# control.net
KiCad netlist of a schematic drawn in EAGLE
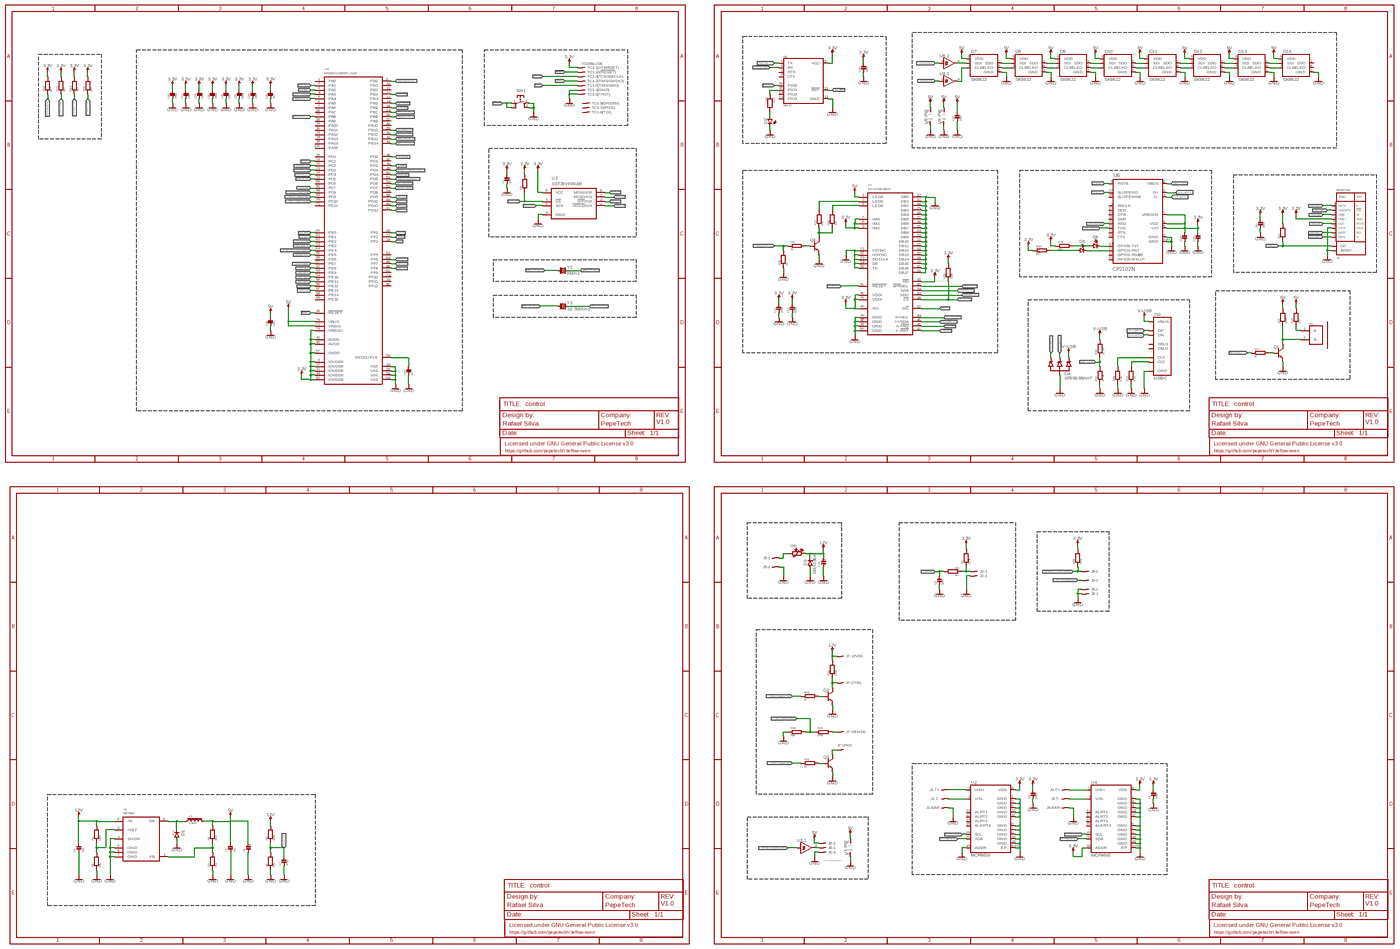
[diagram p0: schematic, sheet 1, overview]
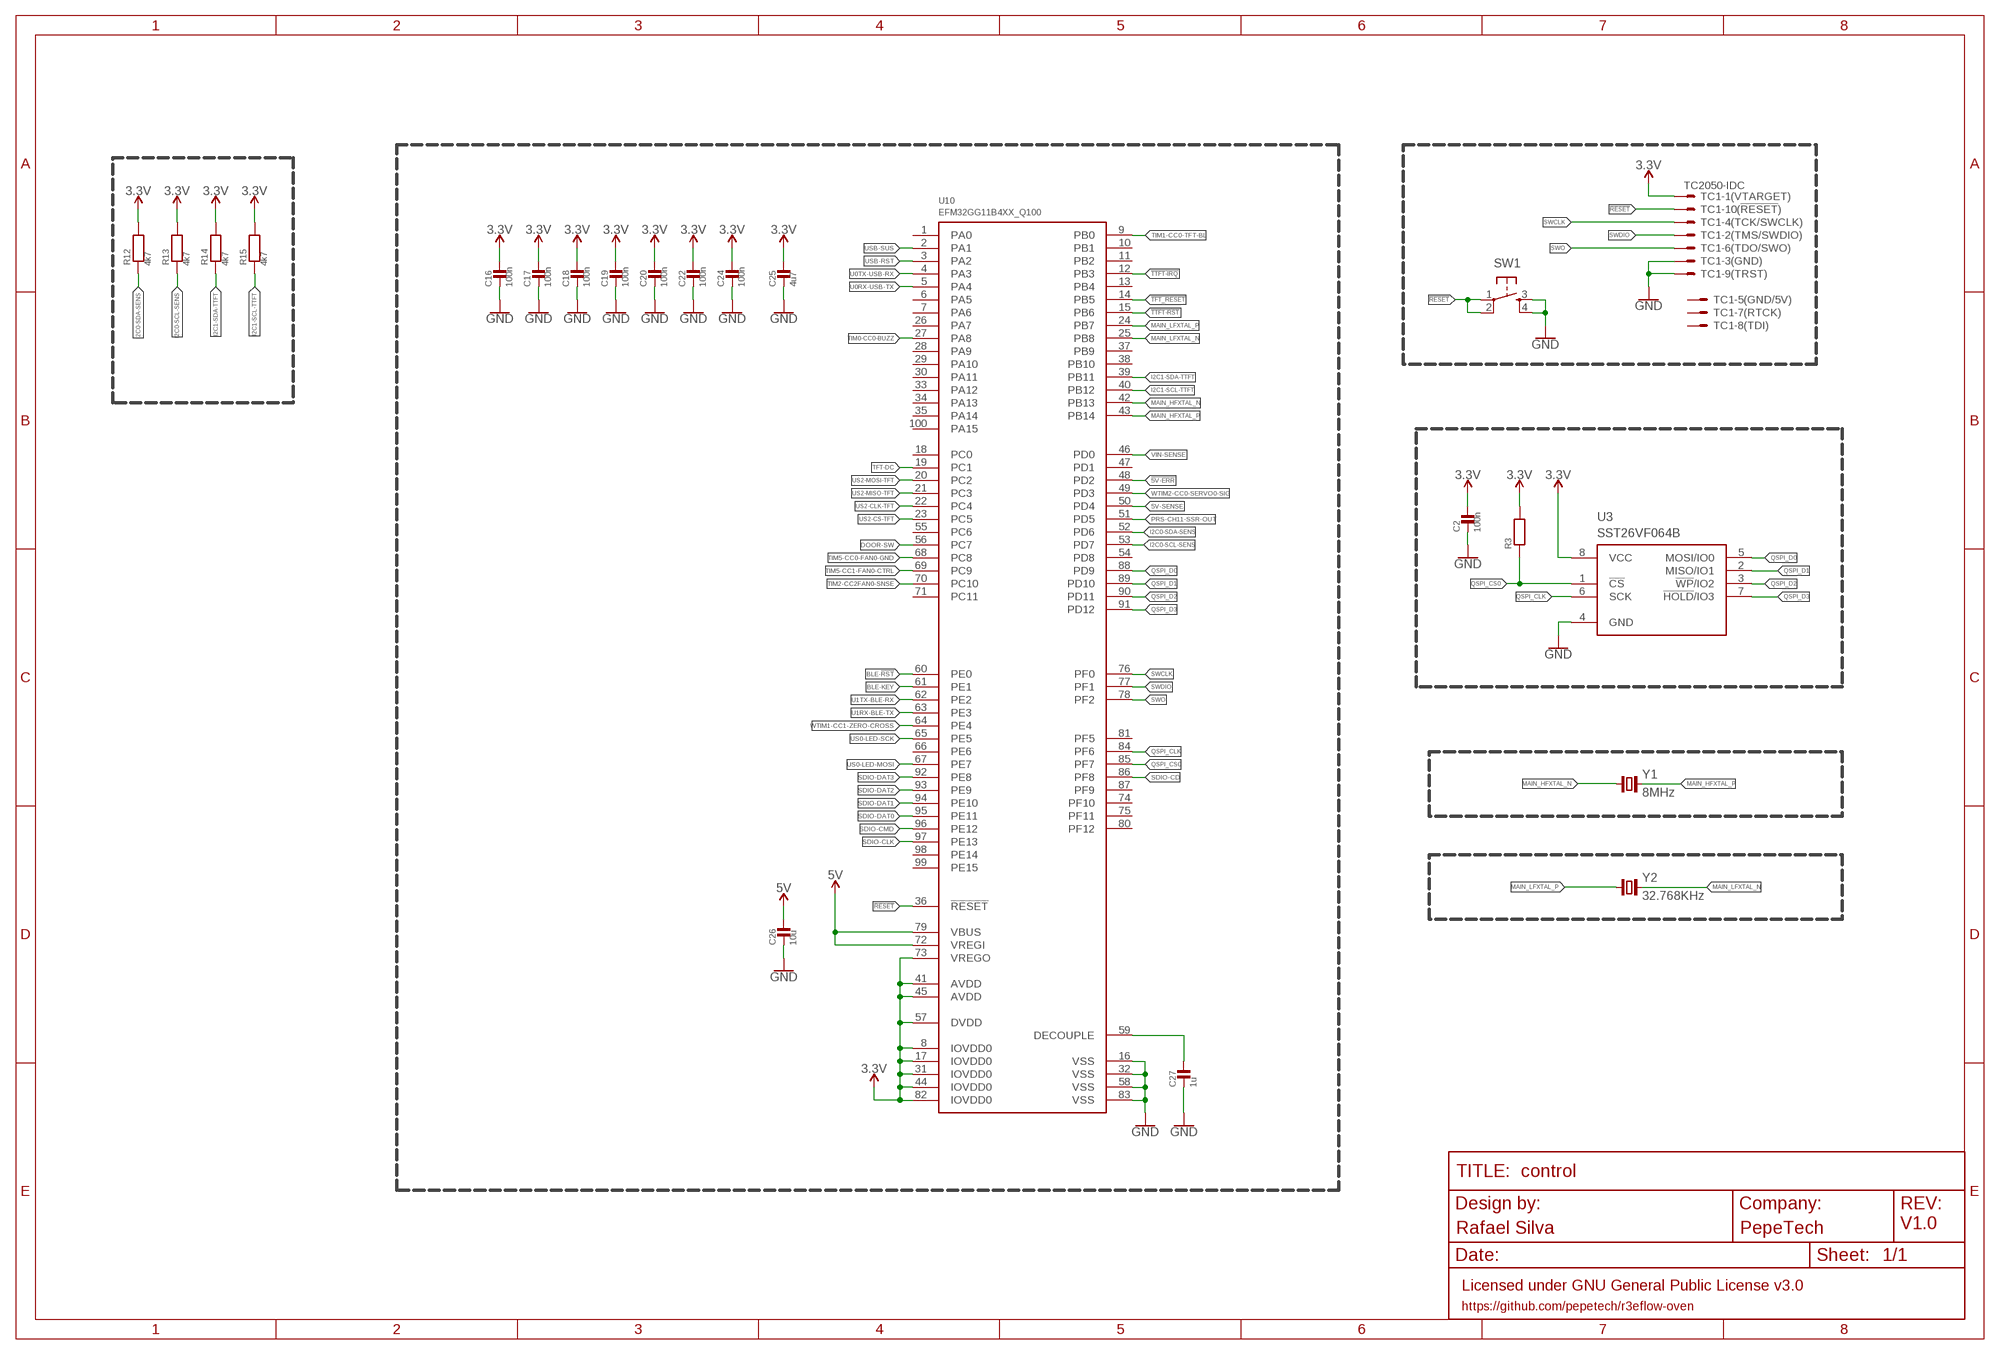
[diagram p1: schematic, sheet 1, part 1 of 4]
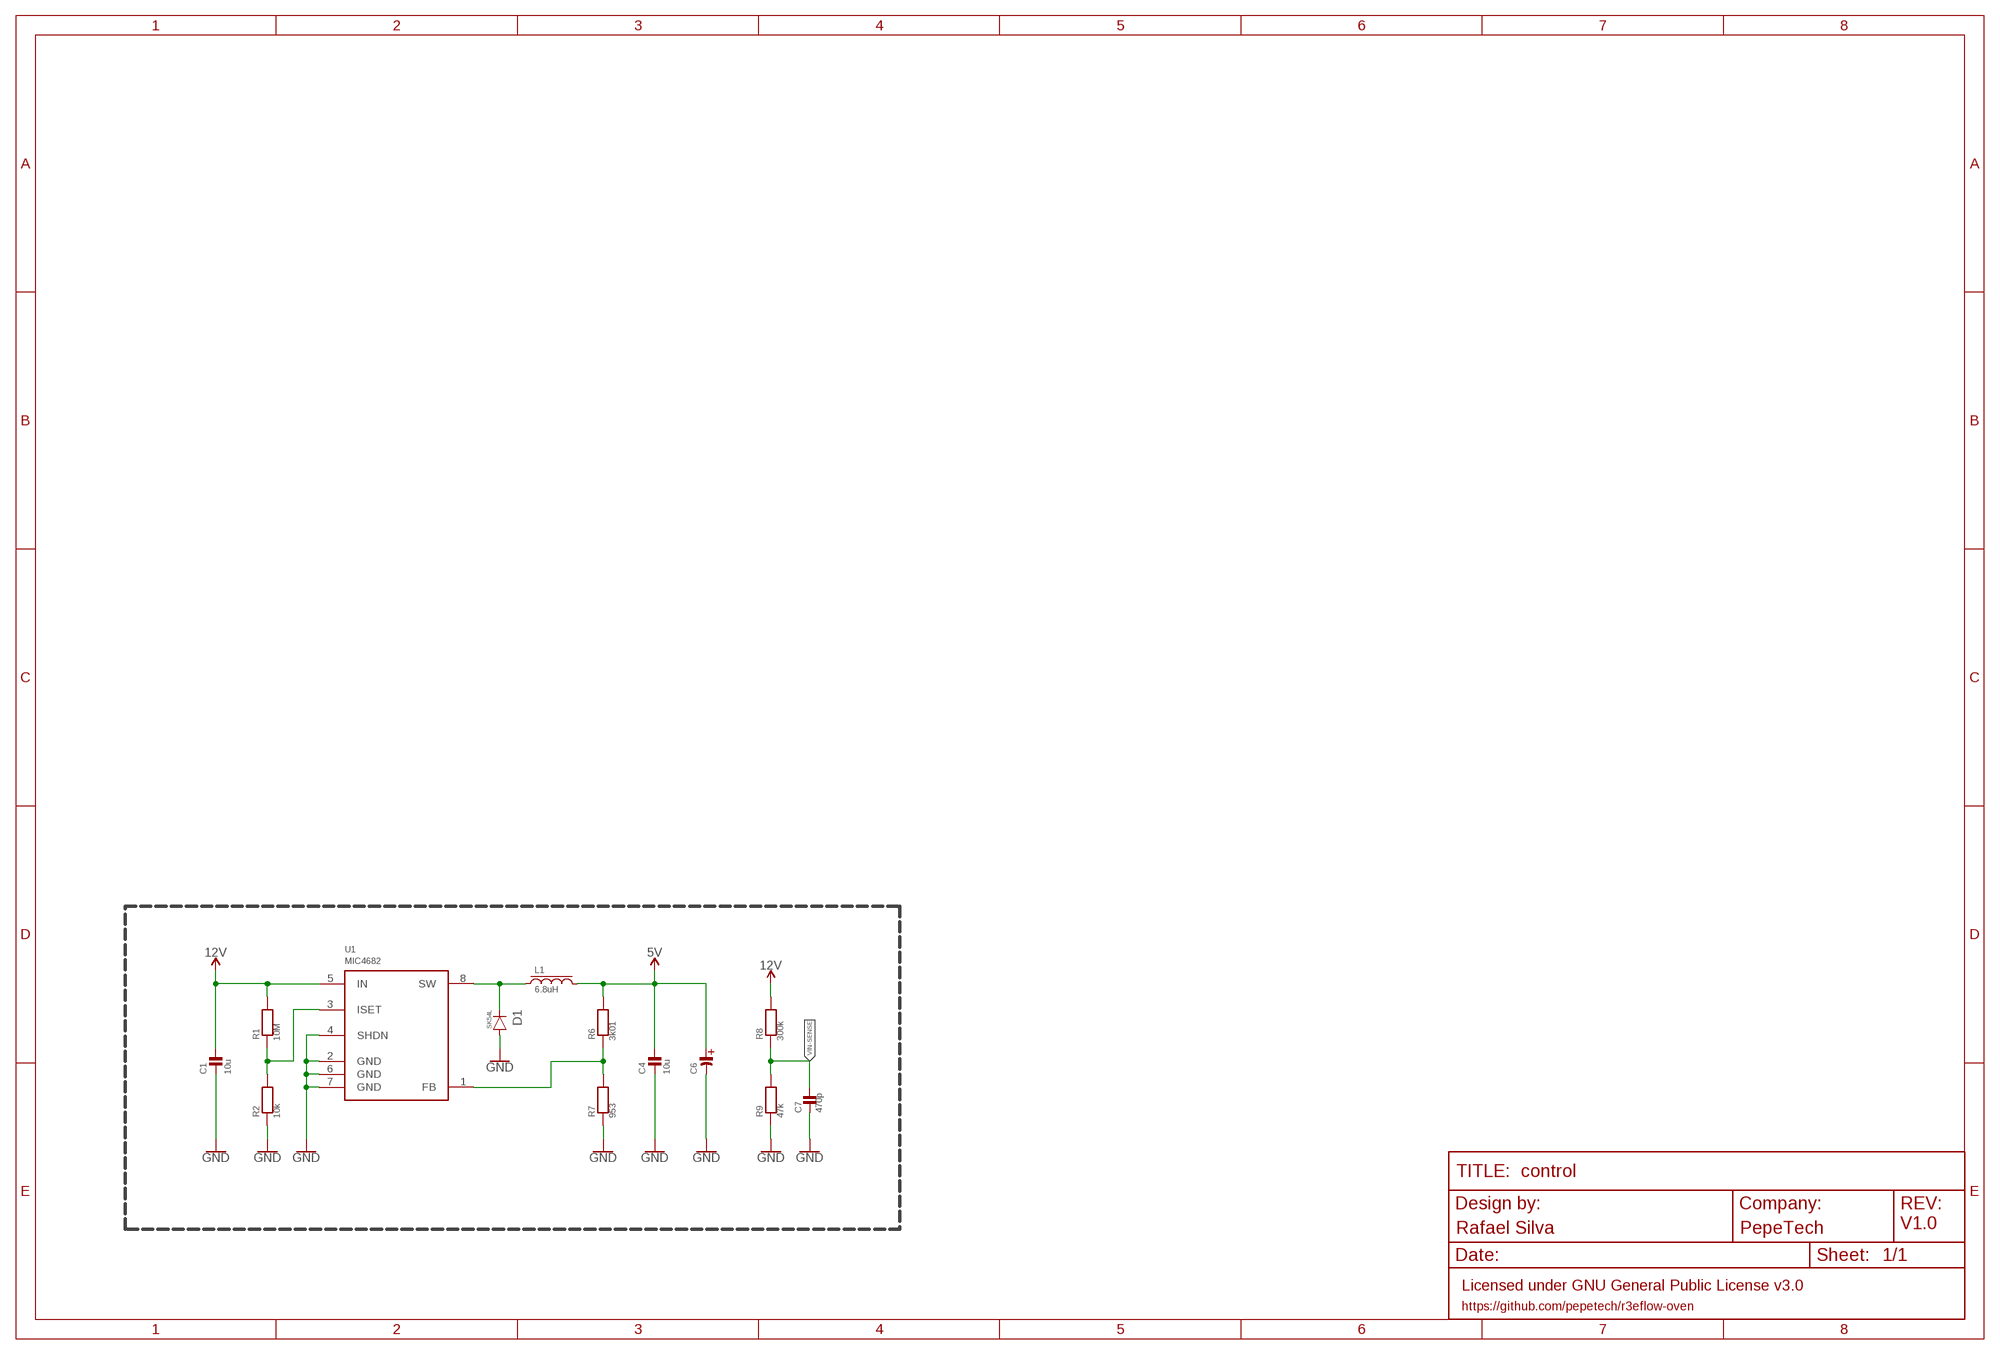
[diagram p2: schematic, sheet 1, part 2 of 4]
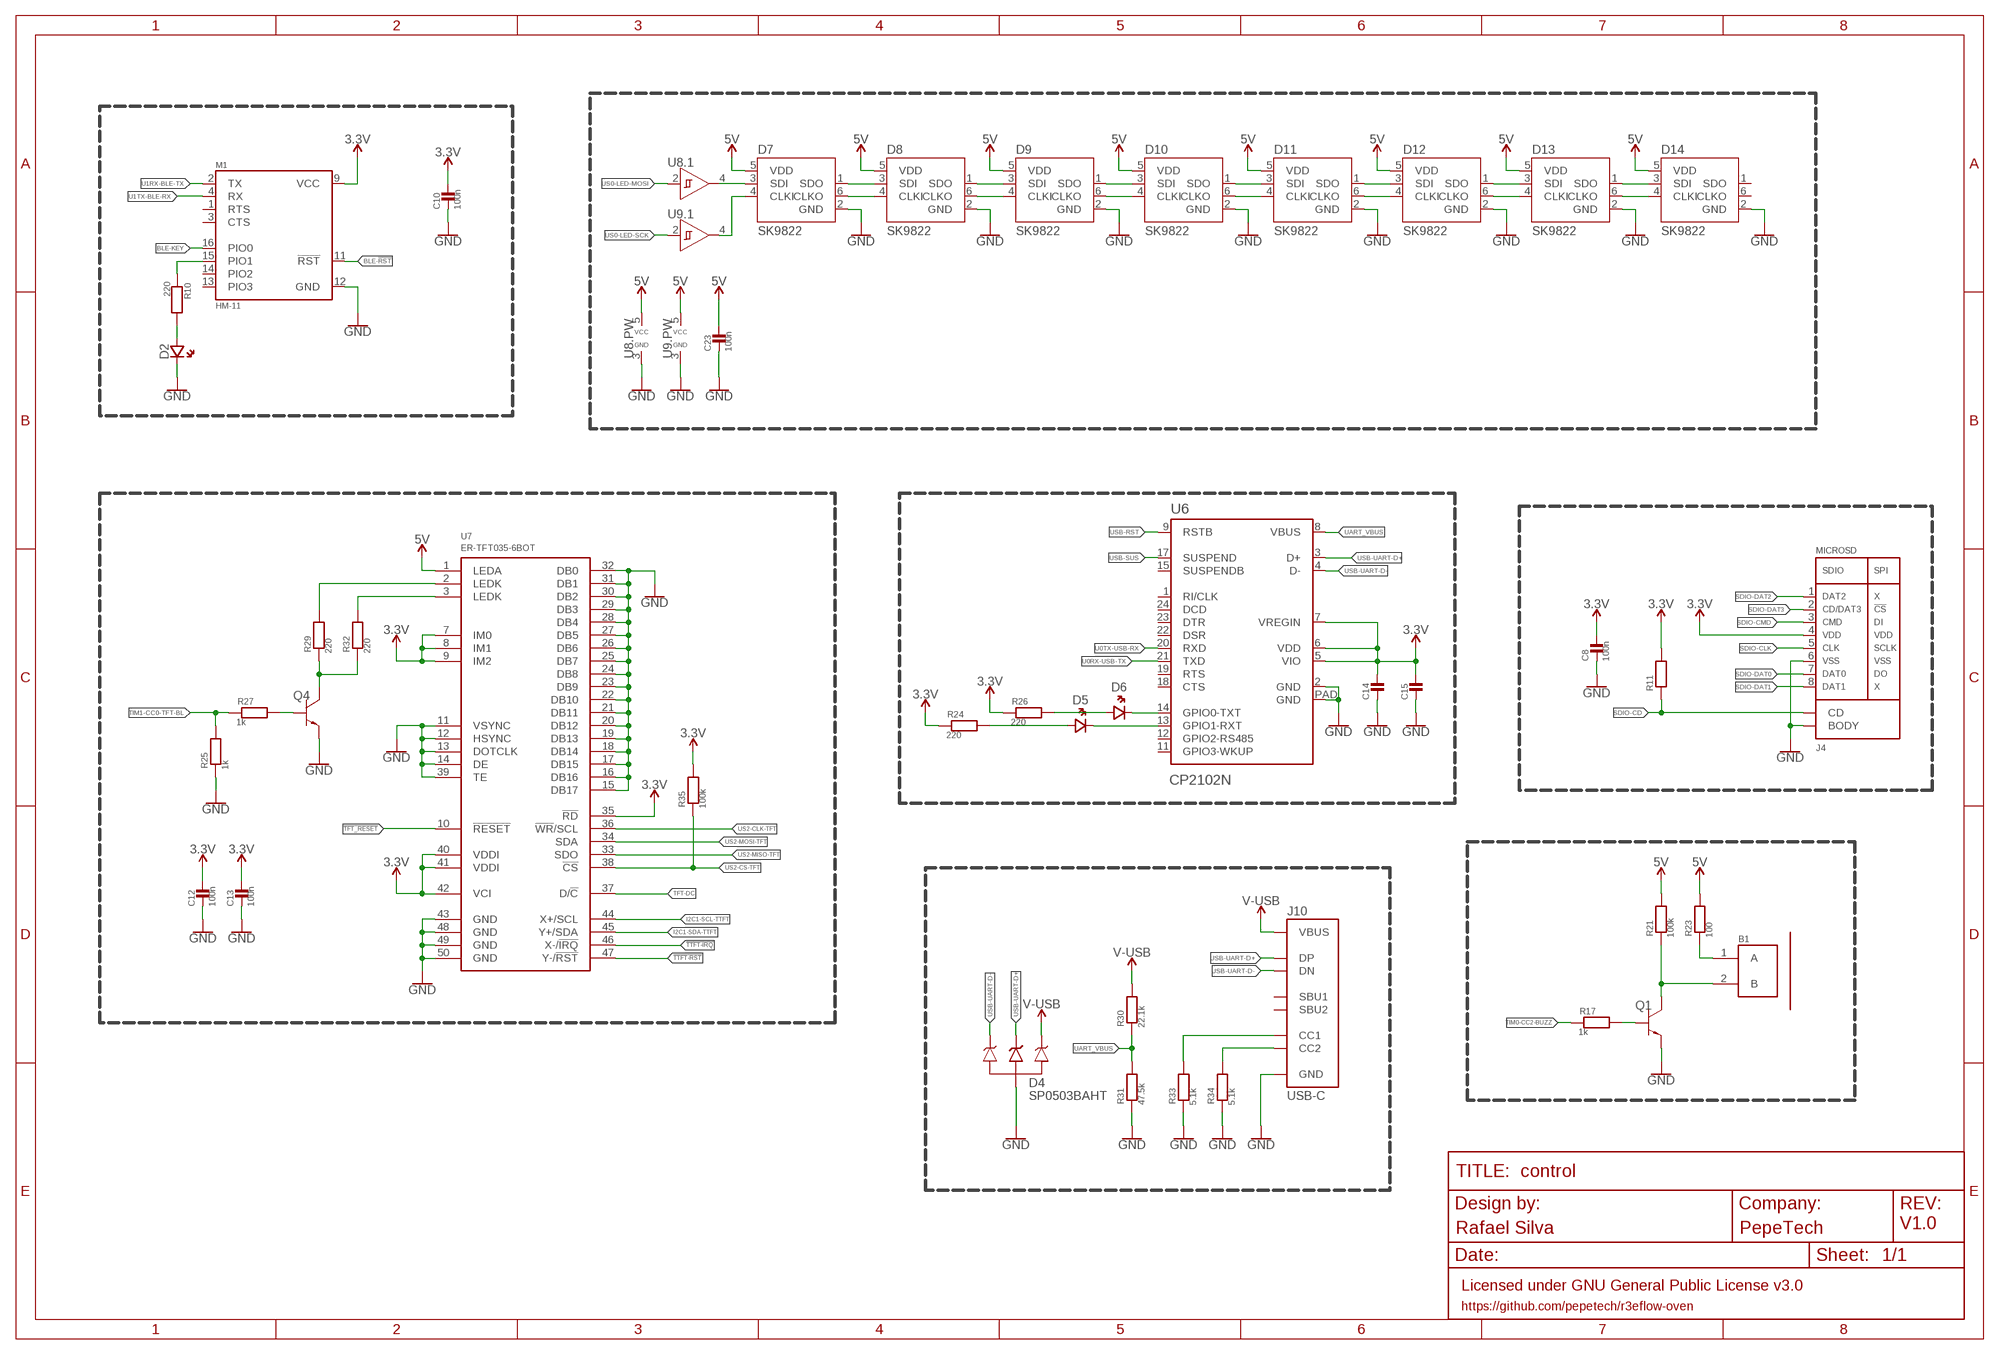
[diagram p3: schematic, sheet 1, part 3 of 4]
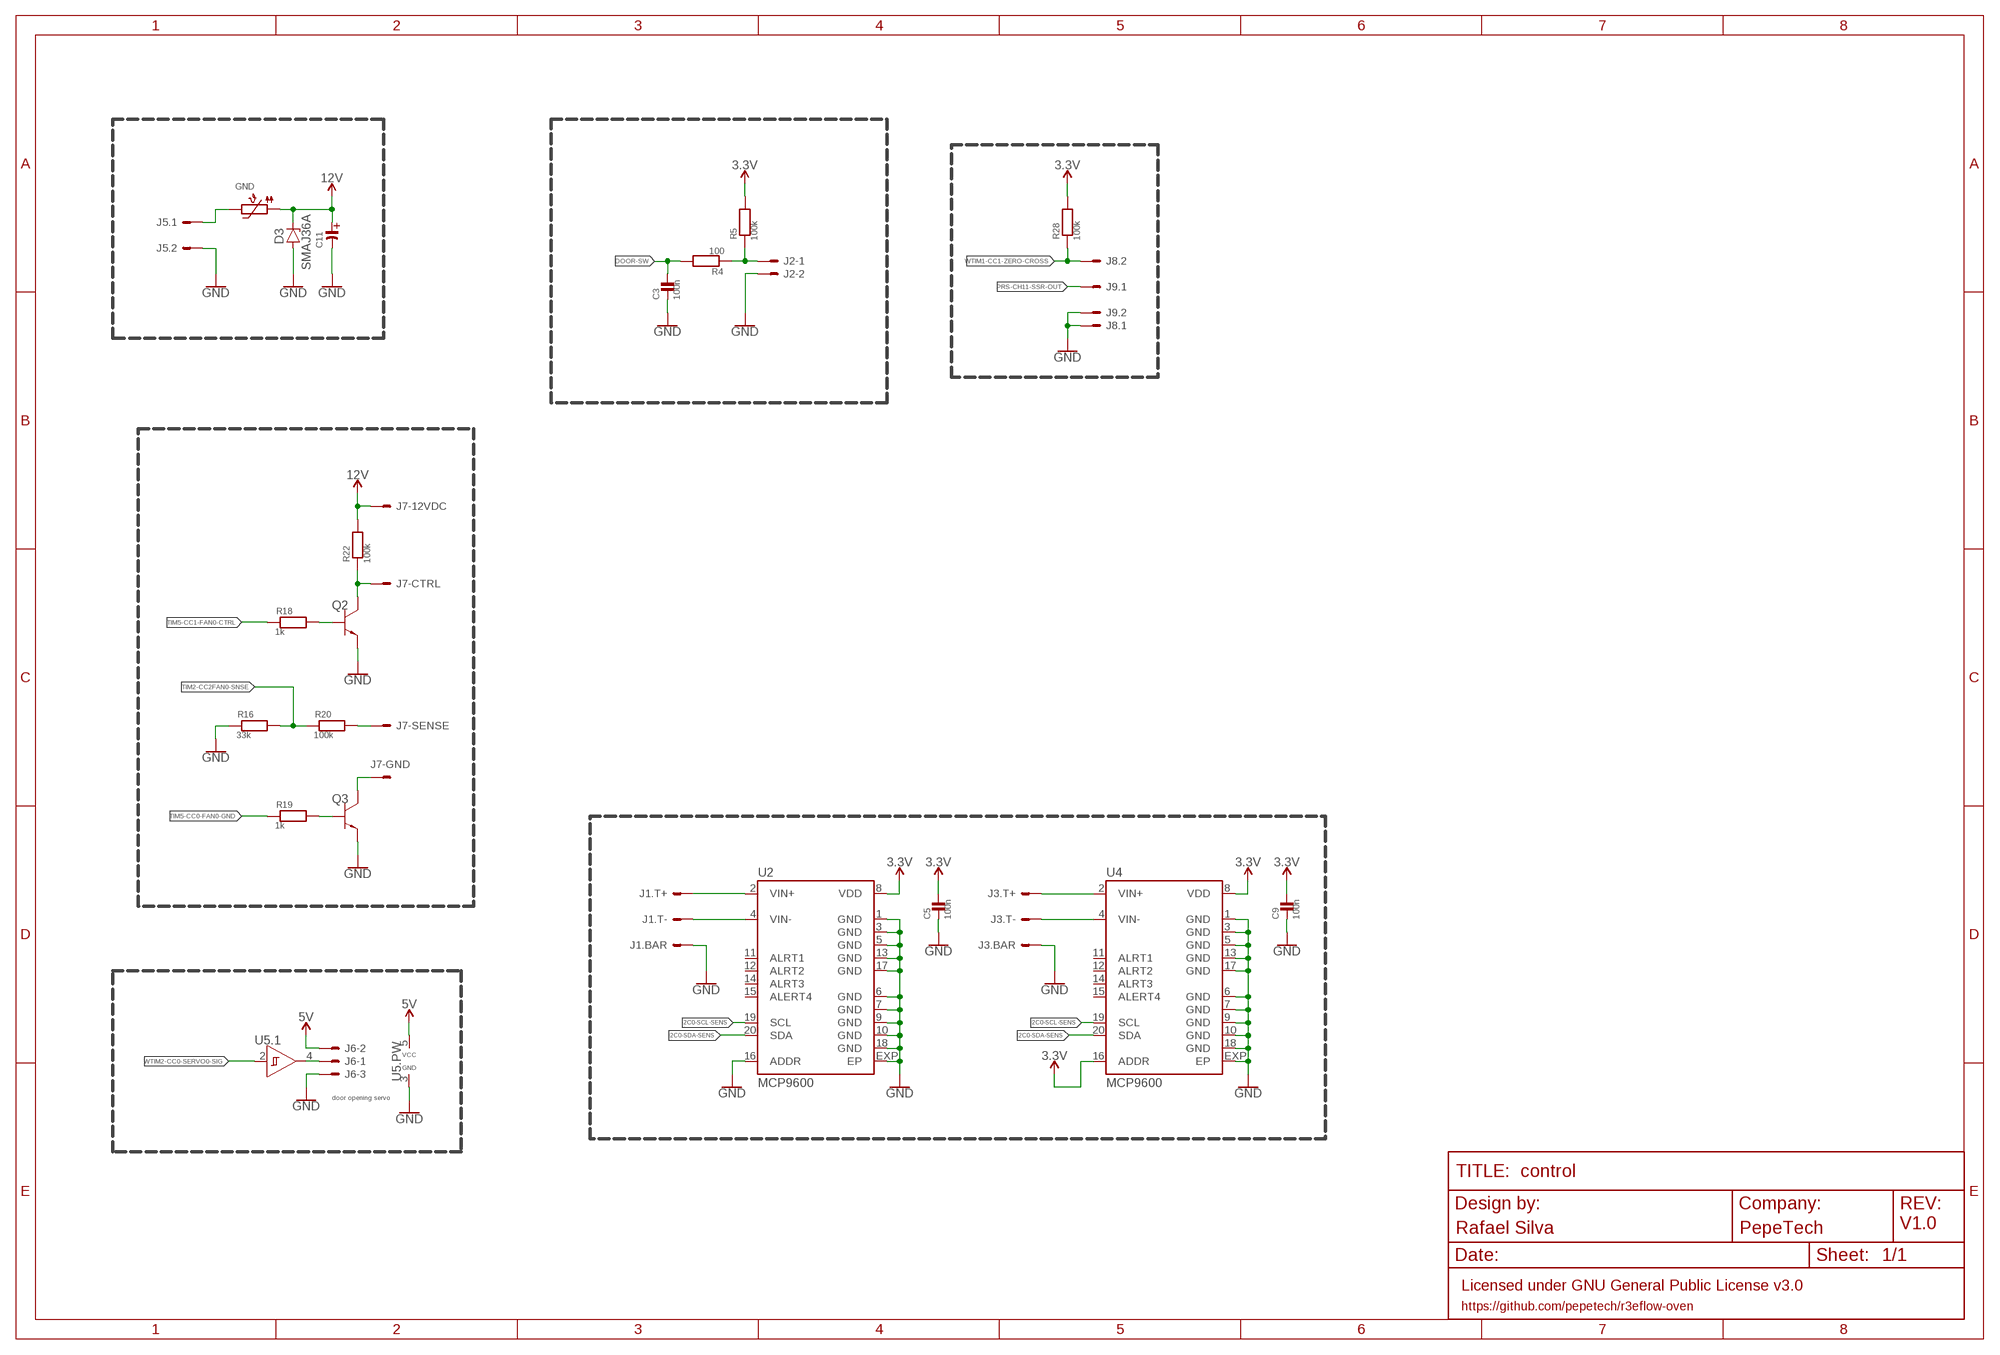
[diagram p4: schematic, sheet 1, part 4 of 4]

(export (version "E")
  (design (tool "Eeschema 10.0.6"))
  (components
    (comp (ref "B1")
      (value "PKLCS1212E2400-R1")
      (footprint "eagle-import:BUZZ_PIEZO_SMD")
      (libsource (lib "eagle-import") (part "PKLCS1212E2400-R1"))
    )
    (comp (ref "C1")
      (value "10u")
      (footprint "eagle-import:0603-MINI")
      (libsource (lib "eagle-import") (part "MLCC0603_MINI"))
    )
    (comp (ref "C2")
      (value "100n")
      (footprint "eagle-import:0603_WAVE")
      (libsource (lib "eagle-import") (part "MLCC0603"))
    )
    (comp (ref "C3")
      (value "100n")
      (footprint "eagle-import:0603_WAVE")
      (libsource (lib "eagle-import") (part "MLCC0603"))
    )
    (comp (ref "C4")
      (value "10u")
      (footprint "eagle-import:0603-MINI")
      (libsource (lib "eagle-import") (part "MLCC0603_MINI"))
    )
    (comp (ref "C5")
      (value "100n")
      (footprint "eagle-import:0603_WAVE")
      (libsource (lib "eagle-import") (part "MLCC0603"))
    )
    (comp (ref "C6")
      (value "220u")
      (footprint "eagle-import:PANASONIC_D")
      (libsource (lib "eagle-import") (part "CAPACITOR_ELD"))
    )
    (comp (ref "C7")
      (value "470p")
      (footprint "eagle-import:0603_WAVE")
      (libsource (lib "eagle-import") (part "MLCC0603"))
    )
    (comp (ref "C8")
      (value "100n")
      (footprint "eagle-import:0603_WAVE")
      (libsource (lib "eagle-import") (part "MLCC0603"))
    )
    (comp (ref "C9")
      (value "100n")
      (footprint "eagle-import:0603_WAVE")
      (libsource (lib "eagle-import") (part "MLCC0603"))
    )
    (comp (ref "C10")
      (value "100n")
      (footprint "eagle-import:0603_WAVE")
      (libsource (lib "eagle-import") (part "MLCC0603"))
    )
    (comp (ref "C11")
      (value "CAPACITOR_ELD")
      (footprint "eagle-import:PANASONIC_D")
      (libsource (lib "eagle-import") (part "CAPACITOR_ELD"))
    )
    (comp (ref "C12")
      (value "100n")
      (footprint "eagle-import:0603_WAVE")
      (libsource (lib "eagle-import") (part "MLCC0603"))
    )
    (comp (ref "C13")
      (value "100n")
      (footprint "eagle-import:0603_WAVE")
      (libsource (lib "eagle-import") (part "MLCC0603"))
    )
    (comp (ref "C14")
      (value "MLCC0603")
      (footprint "eagle-import:0603_WAVE")
      (libsource (lib "eagle-import") (part "MLCC0603"))
    )
    (comp (ref "C15")
      (value "MLCC0603")
      (footprint "eagle-import:0603_WAVE")
      (libsource (lib "eagle-import") (part "MLCC0603"))
    )
    (comp (ref "C16")
      (value "100n")
      (footprint "eagle-import:0603_WAVE")
      (libsource (lib "eagle-import") (part "MLCC0603"))
    )
    (comp (ref "C17")
      (value "100n")
      (footprint "eagle-import:0603_WAVE")
      (libsource (lib "eagle-import") (part "MLCC0603"))
    )
    (comp (ref "C18")
      (value "100n")
      (footprint "eagle-import:0603_WAVE")
      (libsource (lib "eagle-import") (part "MLCC0603"))
    )
    (comp (ref "C19")
      (value "100n")
      (footprint "eagle-import:0603_WAVE")
      (libsource (lib "eagle-import") (part "MLCC0603"))
    )
    (comp (ref "C20")
      (value "100n")
      (footprint "eagle-import:0603_WAVE")
      (libsource (lib "eagle-import") (part "MLCC0603"))
    )
    (comp (ref "C22")
      (value "100n")
      (footprint "eagle-import:0603_WAVE")
      (libsource (lib "eagle-import") (part "MLCC0603"))
    )
    (comp (ref "C23")
      (value "100n")
      (footprint "eagle-import:0603_WAVE")
      (libsource (lib "eagle-import") (part "MLCC0603"))
    )
    (comp (ref "C24")
      (value "100n")
      (footprint "eagle-import:0603_WAVE")
      (libsource (lib "eagle-import") (part "MLCC0603"))
    )
    (comp (ref "C25")
      (value "4u7")
      (footprint "eagle-import:0603_WAVE")
      (libsource (lib "eagle-import") (part "MLCC0603"))
    )
    (comp (ref "C26")
      (value "10u")
      (footprint "eagle-import:0603_WAVE")
      (libsource (lib "eagle-import") (part "MLCC0603"))
    )
    (comp (ref "C27")
      (value "1u")
      (footprint "eagle-import:0603_WAVE")
      (libsource (lib "eagle-import") (part "MLCC0603"))
    )
    (comp (ref "D1")
      (value "SK54L")
      (footprint "eagle-import:DO214AA")
      (libsource (lib "eagle-import") (part "SK54L"))
    )
    (comp (ref "D2")
      (value "LED0603")
      (footprint "eagle-import:CHIPLED_0603")
      (libsource (lib "eagle-import") (part "LED0603"))
    )
    (comp (ref "D3")
      (value "SMAJ36A")
      (footprint "eagle-import:DO214AC")
      (libsource (lib "eagle-import") (part "SMAJ36A"))
    )
    (comp (ref "D4")
      (value "SP0503BAHT")
      (footprint "eagle-import:SOT143")
      (libsource (lib "eagle-import") (part "SP0503BAHT"))
    )
    (comp (ref "D5")
      (value "LED0603")
      (footprint "eagle-import:CHIPLED_0603")
      (libsource (lib "eagle-import") (part "LED0603"))
    )
    (comp (ref "D6")
      (value "LED0603")
      (footprint "eagle-import:CHIPLED_0603")
      (libsource (lib "eagle-import") (part "LED0603"))
    )
    (comp (ref "D7")
      (value "SK9822")
      (footprint "eagle-import:2020")
      (libsource (lib "eagle-import") (part "SK9822"))
    )
    (comp (ref "D8")
      (value "SK9822")
      (footprint "eagle-import:2020")
      (libsource (lib "eagle-import") (part "SK9822"))
    )
    (comp (ref "D9")
      (value "SK9822")
      (footprint "eagle-import:2020")
      (libsource (lib "eagle-import") (part "SK9822"))
    )
    (comp (ref "D10")
      (value "SK9822")
      (footprint "eagle-import:2020")
      (libsource (lib "eagle-import") (part "SK9822"))
    )
    (comp (ref "D11")
      (value "SK9822")
      (footprint "eagle-import:2020")
      (libsource (lib "eagle-import") (part "SK9822"))
    )
    (comp (ref "D12")
      (value "SK9822")
      (footprint "eagle-import:2020")
      (libsource (lib "eagle-import") (part "SK9822"))
    )
    (comp (ref "D13")
      (value "SK9822")
      (footprint "eagle-import:2020")
      (libsource (lib "eagle-import") (part "SK9822"))
    )
    (comp (ref "D14")
      (value "SK9822")
      (footprint "eagle-import:2020")
      (libsource (lib "eagle-import") (part "SK9822"))
    )
    (comp (ref "GND")
      (value "PTC1812")
      (footprint "eagle-import:PTC1812")
      (libsource (lib "eagle-import") (part "PTC1812"))
    )
    (comp (ref "J1")
      (value "PCC-SMP")
      (footprint "eagle-import:PCC-SMP")
      (libsource (lib "eagle-import") (part "PCC-SMP"))
    )
    (comp (ref "J2")
      (value "2X1_2.54")
      (footprint "eagle-import:2X1_2.54")
      (libsource (lib "eagle-import") (part "2X1_2.54"))
    )
    (comp (ref "J3")
      (value "PCC-SMP")
      (footprint "eagle-import:PCC-SMP")
      (libsource (lib "eagle-import") (part "PCC-SMP"))
    )
    (comp (ref "J4")
      (value "MICROSD")
      (footprint "eagle-import:MICRO-SD")
      (libsource (lib "eagle-import") (part "MICROSD"))
    )
    (comp (ref "J5")
      (value "2EDG-2P")
      (footprint "eagle-import:2EDG-2P")
      (libsource (lib "eagle-import") (part "2EDG-2P"))
    )
    (comp (ref "J6")
      (value "3X1_2.54")
      (footprint "eagle-import:3X1_2.54")
      (libsource (lib "eagle-import") (part "3X1_2.54"))
    )
    (comp (ref "J7")
      (value "4P-PC-FAN")
      (footprint "eagle-import:KF2510-3+1P")
      (libsource (lib "eagle-import") (part "4P-PC-FAN"))
    )
    (comp (ref "J8")
      (value "2EDG-2P")
      (footprint "eagle-import:2EDG-2P")
      (libsource (lib "eagle-import") (part "2EDG-2P"))
    )
    (comp (ref "J9")
      (value "2EDG-2P")
      (footprint "eagle-import:2EDG-2P")
      (libsource (lib "eagle-import") (part "2EDG-2P"))
    )
    (comp (ref "J10")
      (value "USB-C")
      (footprint "eagle-import:USB-C")
      (libsource (lib "eagle-import") (part "USB-C"))
    )
    (comp (ref "L1")
      (value "6.8uH")
      (footprint "eagle-import:_1207")
      (libsource (lib "eagle-import") (part "INDUCTOR_1207"))
    )
    (comp (ref "M1")
      (value "HM-11")
      (footprint "eagle-import:HM-11")
      (libsource (lib "eagle-import") (part "HM-11"))
    )
    (comp (ref "Q1")
      (value "BC817-40")
      (footprint "eagle-import:SOT-23-3")
      (libsource (lib "eagle-import") (part "BC817-40"))
    )
    (comp (ref "Q2")
      (value "BC817-40")
      (footprint "eagle-import:SOT-23-3")
      (libsource (lib "eagle-import") (part "BC817-40"))
    )
    (comp (ref "Q3")
      (value "BC817-40")
      (footprint "eagle-import:SOT-23-3")
      (libsource (lib "eagle-import") (part "BC817-40"))
    )
    (comp (ref "Q4")
      (value "BC817-40")
      (footprint "eagle-import:SOT-23-3")
      (libsource (lib "eagle-import") (part "BC817-40"))
    )
    (comp (ref "R1")
      (value "10M")
      (footprint "eagle-import:0603_WAVE")
      (libsource (lib "eagle-import") (part "RESISTOR0603"))
    )
    (comp (ref "R2")
      (value "10k")
      (footprint "eagle-import:0603_WAVE")
      (libsource (lib "eagle-import") (part "RESISTOR0603"))
    )
    (comp (ref "R3")
      (value "RESISTOR0603")
      (footprint "eagle-import:0603_WAVE")
      (libsource (lib "eagle-import") (part "RESISTOR0603"))
    )
    (comp (ref "R4")
      (value "100")
      (footprint "eagle-import:0603_WAVE")
      (libsource (lib "eagle-import") (part "RESISTOR0603"))
    )
    (comp (ref "R5")
      (value "100k")
      (footprint "eagle-import:0603_WAVE")
      (libsource (lib "eagle-import") (part "RESISTOR0603"))
    )
    (comp (ref "R6")
      (value "3k01")
      (footprint "eagle-import:0603_WAVE")
      (libsource (lib "eagle-import") (part "RESISTOR0603"))
    )
    (comp (ref "R7")
      (value "953")
      (footprint "eagle-import:0603_WAVE")
      (libsource (lib "eagle-import") (part "RESISTOR0603"))
    )
    (comp (ref "R8")
      (value "300k")
      (footprint "eagle-import:0603_WAVE")
      (libsource (lib "eagle-import") (part "RESISTOR0603"))
    )
    (comp (ref "R9")
      (value "47k")
      (footprint "eagle-import:0603_WAVE")
      (libsource (lib "eagle-import") (part "RESISTOR0603"))
    )
    (comp (ref "R10")
      (value "220")
      (footprint "eagle-import:0603_WAVE")
      (libsource (lib "eagle-import") (part "RESISTOR0603"))
    )
    (comp (ref "R11")
      (value "RESISTOR0603")
      (footprint "eagle-import:0603_WAVE")
      (libsource (lib "eagle-import") (part "RESISTOR0603"))
    )
    (comp (ref "R12")
      (value "4k7")
      (footprint "eagle-import:0603_WAVE")
      (libsource (lib "eagle-import") (part "RESISTOR0603"))
    )
    (comp (ref "R13")
      (value "4k7")
      (footprint "eagle-import:0603_WAVE")
      (libsource (lib "eagle-import") (part "RESISTOR0603"))
    )
    (comp (ref "R14")
      (value "4k7")
      (footprint "eagle-import:0603_WAVE")
      (libsource (lib "eagle-import") (part "RESISTOR0603"))
    )
    (comp (ref "R15")
      (value "4k7")
      (footprint "eagle-import:0603_WAVE")
      (libsource (lib "eagle-import") (part "RESISTOR0603"))
    )
    (comp (ref "R16")
      (value "33k")
      (footprint "eagle-import:0603_WAVE")
      (libsource (lib "eagle-import") (part "RESISTOR0603"))
    )
    (comp (ref "R17")
      (value "1k")
      (footprint "eagle-import:0603_WAVE")
      (libsource (lib "eagle-import") (part "RESISTOR0603"))
    )
    (comp (ref "R18")
      (value "1k")
      (footprint "eagle-import:0603_WAVE")
      (libsource (lib "eagle-import") (part "RESISTOR0603"))
    )
    (comp (ref "R19")
      (value "1k")
      (footprint "eagle-import:0603_WAVE")
      (libsource (lib "eagle-import") (part "RESISTOR0603"))
    )
    (comp (ref "R20")
      (value "100k")
      (footprint "eagle-import:0603_WAVE")
      (libsource (lib "eagle-import") (part "RESISTOR0603"))
    )
    (comp (ref "R21")
      (value "100k")
      (footprint "eagle-import:0603_WAVE")
      (libsource (lib "eagle-import") (part "RESISTOR0603"))
    )
    (comp (ref "R22")
      (value "100k")
      (footprint "eagle-import:0603_WAVE")
      (libsource (lib "eagle-import") (part "RESISTOR0603"))
    )
    (comp (ref "R23")
      (value "100")
      (footprint "eagle-import:0603_WAVE")
      (libsource (lib "eagle-import") (part "RESISTOR0603"))
    )
    (comp (ref "R24")
      (value "220")
      (footprint "eagle-import:0603_WAVE")
      (libsource (lib "eagle-import") (part "RESISTOR0603"))
    )
    (comp (ref "R25")
      (value "1k")
      (footprint "eagle-import:0603_WAVE")
      (libsource (lib "eagle-import") (part "RESISTOR0603"))
    )
    (comp (ref "R26")
      (value "220")
      (footprint "eagle-import:0603_WAVE")
      (libsource (lib "eagle-import") (part "RESISTOR0603"))
    )
    (comp (ref "R27")
      (value "1k")
      (footprint "eagle-import:0603_WAVE")
      (libsource (lib "eagle-import") (part "RESISTOR0603"))
    )
    (comp (ref "R28")
      (value "100k")
      (footprint "eagle-import:0603_WAVE")
      (libsource (lib "eagle-import") (part "RESISTOR0603"))
    )
    (comp (ref "R29")
      (value "220")
      (footprint "eagle-import:0603_WAVE")
      (libsource (lib "eagle-import") (part "RESISTOR0603"))
    )
    (comp (ref "R30")
      (value "22.1k")
      (footprint "eagle-import:0603_WAVE")
      (libsource (lib "eagle-import") (part "RESISTOR0603"))
    )
    (comp (ref "R31")
      (value "47.5k")
      (footprint "eagle-import:0603_WAVE")
      (libsource (lib "eagle-import") (part "RESISTOR0603"))
    )
    (comp (ref "R32")
      (value "220")
      (footprint "eagle-import:0603_WAVE")
      (libsource (lib "eagle-import") (part "RESISTOR0603"))
    )
    (comp (ref "R33")
      (value "5.1k")
      (footprint "eagle-import:0603_WAVE")
      (libsource (lib "eagle-import") (part "RESISTOR0603"))
    )
    (comp (ref "R34")
      (value "5.1k")
      (footprint "eagle-import:0603_WAVE")
      (libsource (lib "eagle-import") (part "RESISTOR0603"))
    )
    (comp (ref "R35")
      (value "100k")
      (footprint "eagle-import:0603_WAVE")
      (libsource (lib "eagle-import") (part "RESISTOR0603"))
    )
    (comp (ref "SW1")
      (value "PUSH_BUTTON")
      (footprint "eagle-import:PUSH_BUTTON")
      (libsource (lib "eagle-import") (part "PUSH_BUTTON"))
    )
    (comp (ref "TC1")
      (value "TC2050-IDC")
      (footprint "eagle-import:TC2050-IDC")
      (libsource (lib "eagle-import") (part "TC2050-IDC"))
    )
    (comp (ref "U1")
      (value "MIC4682")
      (footprint "eagle-import:SOIC8")
      (libsource (lib "eagle-import") (part "MIC4682"))
    )
    (comp (ref "U2")
      (value "MCP9600")
      (footprint "eagle-import:TQFN20-5X5")
      (libsource (lib "eagle-import") (part "MCP9600"))
    )
    (comp (ref "U3")
      (value "SST26VF064B")
      (footprint "eagle-import:WSOIC8")
      (libsource (lib "eagle-import") (part "SST26VF064B"))
    )
    (comp (ref "U4")
      (value "MCP9600")
      (footprint "eagle-import:TQFN20-5X5")
      (libsource (lib "eagle-import") (part "MCP9600"))
    )
    (comp (ref "U5")
      (value "74LVC1G17")
      (footprint "eagle-import:SC70-5")
      (libsource (lib "eagle-import") (part "74LVC1G17"))
    )
    (comp (ref "U6")
      (value "CP2102N")
      (footprint "eagle-import:QFN24")
      (libsource (lib "eagle-import") (part "CP2102N"))
    )
    (comp (ref "U7")
      (value "ER-TFT035-6BOT")
      (footprint "eagle-import:ZIF50-TFT_BACK")
      (libsource (lib "eagle-import") (part "ER-TFT035-6BOT"))
    )
    (comp (ref "U8")
      (value "74LVC1G17")
      (footprint "eagle-import:SC70-5")
      (libsource (lib "eagle-import") (part "74LVC1G17"))
    )
    (comp (ref "U9")
      (value "74LVC1G17")
      (footprint "eagle-import:SC70-5")
      (libsource (lib "eagle-import") (part "74LVC1G17"))
    )
    (comp (ref "U10")
      (value "EFM32GG11B4XX_Q100")
      (footprint "eagle-import:QFP100")
      (libsource (lib "eagle-import") (part "EFM32GG11B4XX_Q100"))
    )
    (comp (ref "Y1")
      (value "8MHz")
      (footprint "eagle-import:2-SMD-5X3")
      (libsource (lib "eagle-import") (part "CRYSTALNX5032GA"))
    )
    (comp (ref "Y2")
      (value "32.768KHz")
      (footprint "eagle-import:CM200S")
      (libsource (lib "eagle-import") (part "CRYSTALCM200S"))
    )
  )
  (nets
    (net (code "1") (name "/BLE-~{RST}") (class "Default")
      (node (ref "M1") (pin "11") (pinfunction "~{RST}_11") (pintype "bidirectional"))
      (node (ref "U10") (pin "60") (pinfunction "PE0_60") (pintype "bidirectional"))
    )
    (net (code "2") (name "/~{5V-ERR}") (class "Default")
      (node (ref "U10") (pin "48") (pinfunction "PD2_48") (pintype "bidirectional"))
    )
    (net (code "3") (name "/~{RESET}") (class "Default")
      (node (ref "SW1") (pin "1") (pinfunction "1_1") (pintype "passive"))
      (node (ref "SW1") (pin "2") (pinfunction "2_2") (pintype "passive"))
      (node (ref "TC1") (pin "10") (pinfunction "S_10") (pintype "passive"))
      (node (ref "U10") (pin "36") (pinfunction "~{RESET}_36") (pintype "bidirectional"))
    )
    (net (code "4") (name "/~{TFT_RESET}") (class "Default")
      (node (ref "U10") (pin "14") (pinfunction "PB5_14") (pintype "bidirectional"))
      (node (ref "U7") (pin "10") (pinfunction "~{RESET}_10") (pintype "bidirectional"))
    )
    (net (code "5") (name "/~{TTFT-IRQ}") (class "Default")
      (node (ref "U10") (pin "12") (pinfunction "PB3_12") (pintype "bidirectional"))
      (node (ref "U7") (pin "46") (pinfunction "X-/~{IRQ}_46") (pintype "bidirectional"))
    )
    (net (code "6") (name "/~{TTFT-RST}") (class "Default")
      (node (ref "U10") (pin "15") (pinfunction "PB6_15") (pintype "bidirectional"))
      (node (ref "U7") (pin "47") (pinfunction "Y-/~{RST}_47") (pintype "bidirectional"))
    )
    (net (code "7") (name "3.3V") (class "Default")
      (node (ref "C10") (pin "P$1") (pinfunction "P$1_P$1") (pintype "bidirectional"))
      (node (ref "C12") (pin "P$1") (pinfunction "P$1_P$1") (pintype "bidirectional"))
      (node (ref "C13") (pin "P$1") (pinfunction "P$1_P$1") (pintype "bidirectional"))
      (node (ref "C14") (pin "P$1") (pinfunction "P$1_P$1") (pintype "bidirectional"))
      (node (ref "C15") (pin "P$1") (pinfunction "P$1_P$1") (pintype "bidirectional"))
      (node (ref "C16") (pin "P$1") (pinfunction "P$1_P$1") (pintype "bidirectional"))
      (node (ref "C17") (pin "P$1") (pinfunction "P$1_P$1") (pintype "bidirectional"))
      (node (ref "C18") (pin "P$1") (pinfunction "P$1_P$1") (pintype "bidirectional"))
      (node (ref "C19") (pin "P$1") (pinfunction "P$1_P$1") (pintype "bidirectional"))
      (node (ref "C2") (pin "P$1") (pinfunction "P$1_P$1") (pintype "bidirectional"))
      (node (ref "C20") (pin "P$1") (pinfunction "P$1_P$1") (pintype "bidirectional"))
      (node (ref "C22") (pin "P$1") (pinfunction "P$1_P$1") (pintype "bidirectional"))
      (node (ref "C24") (pin "P$1") (pinfunction "P$1_P$1") (pintype "bidirectional"))
      (node (ref "C25") (pin "P$1") (pinfunction "P$1_P$1") (pintype "bidirectional"))
      (node (ref "C5") (pin "P$1") (pinfunction "P$1_P$1") (pintype "bidirectional"))
      (node (ref "C8") (pin "P$1") (pinfunction "P$1_P$1") (pintype "bidirectional"))
      (node (ref "C9") (pin "P$1") (pinfunction "P$1_P$1") (pintype "bidirectional"))
      (node (ref "J4") (pin "4") (pinfunction "4_4") (pintype "bidirectional"))
      (node (ref "M1") (pin "9") (pinfunction "VCC_9") (pintype "bidirectional"))
      (node (ref "R11") (pin "P$2") (pinfunction "P$2_P$2") (pintype "bidirectional"))
      (node (ref "R12") (pin "P$2") (pinfunction "P$2_P$2") (pintype "bidirectional"))
      (node (ref "R13") (pin "P$2") (pinfunction "P$2_P$2") (pintype "bidirectional"))
      (node (ref "R14") (pin "P$2") (pinfunction "P$2_P$2") (pintype "bidirectional"))
      (node (ref "R15") (pin "P$2") (pinfunction "P$2_P$2") (pintype "bidirectional"))
      (node (ref "R24") (pin "P$1") (pinfunction "P$1_P$1") (pintype "bidirectional"))
      (node (ref "R26") (pin "P$1") (pinfunction "P$1_P$1") (pintype "bidirectional"))
      (node (ref "R28") (pin "P$2") (pinfunction "P$2_P$2") (pintype "bidirectional"))
      (node (ref "R3") (pin "P$2") (pinfunction "P$2_P$2") (pintype "bidirectional"))
      (node (ref "R35") (pin "P$2") (pinfunction "P$2_P$2") (pintype "bidirectional"))
      (node (ref "R5") (pin "P$2") (pinfunction "P$2_P$2") (pintype "bidirectional"))
      (node (ref "TC1") (pin "1") (pinfunction "S_1") (pintype "passive"))
      (node (ref "U10") (pin "17") (pinfunction "IOVDD0_17") (pintype "bidirectional"))
      (node (ref "U10") (pin "31") (pinfunction "IOVDD0_31") (pintype "bidirectional"))
      (node (ref "U10") (pin "41") (pinfunction "AVDD_41") (pintype "bidirectional"))
      (node (ref "U10") (pin "44") (pinfunction "IOVDD0_44") (pintype "bidirectional"))
      (node (ref "U10") (pin "45") (pinfunction "AVDD_45") (pintype "bidirectional"))
      (node (ref "U10") (pin "57") (pinfunction "DVDD_57") (pintype "bidirectional"))
      (node (ref "U10") (pin "73") (pinfunction "VREGO_73") (pintype "bidirectional"))
      (node (ref "U10") (pin "8") (pinfunction "IOVDD0_8") (pintype "bidirectional"))
      (node (ref "U10") (pin "82") (pinfunction "IOVDD0_82") (pintype "bidirectional"))
      (node (ref "U2") (pin "8") (pinfunction "VDD_8") (pintype "bidirectional"))
      (node (ref "U3") (pin "8") (pinfunction "VCC_8") (pintype "power_in"))
      (node (ref "U4") (pin "16") (pinfunction "ADDR_16") (pintype "bidirectional"))
      (node (ref "U4") (pin "8") (pinfunction "VDD_8") (pintype "bidirectional"))
      (node (ref "U6") (pin "5") (pinfunction "VIO_5") (pintype "bidirectional"))
      (node (ref "U6") (pin "6") (pinfunction "VDD_6") (pintype "bidirectional"))
      (node (ref "U6") (pin "7") (pinfunction "VREGIN_7") (pintype "bidirectional"))
      (node (ref "U7") (pin "35") (pinfunction "~{RD}_35") (pintype "bidirectional"))
      (node (ref "U7") (pin "40") (pinfunction "VDDI_40") (pintype "bidirectional"))
      (node (ref "U7") (pin "41") (pinfunction "VDDI_41") (pintype "bidirectional"))
      (node (ref "U7") (pin "42") (pinfunction "VCI_42") (pintype "bidirectional"))
      (node (ref "U7") (pin "7") (pinfunction "IM0_7") (pintype "bidirectional"))
      (node (ref "U7") (pin "8") (pinfunction "IM1_8") (pintype "bidirectional"))
      (node (ref "U7") (pin "9") (pinfunction "IM2_9") (pintype "bidirectional"))
    )
    (net (code "8") (name "5V") (class "Default")
      (node (ref "C23") (pin "P$1") (pinfunction "P$1_P$1") (pintype "bidirectional"))
      (node (ref "C26") (pin "P$1") (pinfunction "P$1_P$1") (pintype "bidirectional"))
      (node (ref "C4") (pin "1") (pinfunction "P$1_1") (pintype "bidirectional"))
      (node (ref "C6") (pin "+") (pinfunction "AN_+") (pintype "bidirectional"))
      (node (ref "D10") (pin "5") (pinfunction "VDD_5") (pintype "bidirectional"))
      (node (ref "D11") (pin "5") (pinfunction "VDD_5") (pintype "bidirectional"))
      (node (ref "D12") (pin "5") (pinfunction "VDD_5") (pintype "bidirectional"))
      (node (ref "D13") (pin "5") (pinfunction "VDD_5") (pintype "bidirectional"))
      (node (ref "D14") (pin "5") (pinfunction "VDD_5") (pintype "bidirectional"))
      (node (ref "D7") (pin "5") (pinfunction "VDD_5") (pintype "bidirectional"))
      (node (ref "D8") (pin "5") (pinfunction "VDD_5") (pintype "bidirectional"))
      (node (ref "D9") (pin "5") (pinfunction "VDD_5") (pintype "bidirectional"))
      (node (ref "J6") (pin "P$2") (pinfunction "S_P$2") (pintype "passive"))
      (node (ref "L1") (pin "2") (pinfunction "P$2_2") (pintype "bidirectional"))
      (node (ref "R21") (pin "P$2") (pinfunction "P$2_P$2") (pintype "bidirectional"))
      (node (ref "R23") (pin "P$2") (pinfunction "P$2_P$2") (pintype "bidirectional"))
      (node (ref "R6") (pin "P$2") (pinfunction "P$2_P$2") (pintype "bidirectional"))
      (node (ref "U10") (pin "72") (pinfunction "VREGI_72") (pintype "bidirectional"))
      (node (ref "U10") (pin "79") (pinfunction "VBUS_79") (pintype "bidirectional"))
      (node (ref "U5") (pin "5") (pinfunction "VCC_5") (pintype "bidirectional"))
      (node (ref "U7") (pin "1") (pinfunction "LEDA_1") (pintype "bidirectional"))
      (node (ref "U8") (pin "5") (pinfunction "VCC_5") (pintype "bidirectional"))
      (node (ref "U9") (pin "5") (pinfunction "VCC_5") (pintype "bidirectional"))
    )
    (net (code "9") (name "5V-SENSE") (class "Default")
      (node (ref "U10") (pin "50") (pinfunction "PD4_50") (pintype "bidirectional"))
    )
    (net (code "10") (name "12V") (class "Default")
      (node (ref "C1") (pin "1") (pinfunction "P$1_1") (pintype "bidirectional"))
      (node (ref "C11") (pin "+") (pinfunction "AN_+") (pintype "bidirectional"))
      (node (ref "D3") (pin "C") (pinfunction "C_C") (pintype "passive"))
      (node (ref "GND") (pin "P$1") (pinfunction "1_P$1") (pintype "passive"))
      (node (ref "J7") (pin "2") (pinfunction "S_2") (pintype "passive"))
      (node (ref "R1") (pin "P$2") (pinfunction "P$2_P$2") (pintype "bidirectional"))
      (node (ref "R22") (pin "P$2") (pinfunction "P$2_P$2") (pintype "bidirectional"))
      (node (ref "R8") (pin "P$2") (pinfunction "P$2_P$2") (pintype "bidirectional"))
      (node (ref "U1") (pin "5") (pinfunction "IN_5") (pintype "bidirectional"))
    )
    (net (code "11") (name "BLE-KEY") (class "Default")
      (node (ref "M1") (pin "16") (pinfunction "PIO0_16") (pintype "bidirectional"))
      (node (ref "U10") (pin "61") (pinfunction "PE1_61") (pintype "bidirectional"))
    )
    (net (code "12") (name "DOOR-SW") (class "Default")
      (node (ref "C3") (pin "P$1") (pinfunction "P$1_P$1") (pintype "bidirectional"))
      (node (ref "R4") (pin "P$2") (pinfunction "P$2_P$2") (pintype "bidirectional"))
      (node (ref "U10") (pin "56") (pinfunction "PC7_56") (pintype "bidirectional"))
    )
    (net (code "13") (name "GND") (class "Default")
      (node (ref "C1") (pin "2") (pinfunction "P$2_2") (pintype "bidirectional"))
      (node (ref "C10") (pin "P$2") (pinfunction "P$2_P$2") (pintype "bidirectional"))
      (node (ref "C11") (pin "-") (pinfunction "CA_-") (pintype "bidirectional"))
      (node (ref "C12") (pin "P$2") (pinfunction "P$2_P$2") (pintype "bidirectional"))
      (node (ref "C13") (pin "P$2") (pinfunction "P$2_P$2") (pintype "bidirectional"))
      (node (ref "C14") (pin "P$2") (pinfunction "P$2_P$2") (pintype "bidirectional"))
      (node (ref "C15") (pin "P$2") (pinfunction "P$2_P$2") (pintype "bidirectional"))
      (node (ref "C16") (pin "P$2") (pinfunction "P$2_P$2") (pintype "bidirectional"))
      (node (ref "C17") (pin "P$2") (pinfunction "P$2_P$2") (pintype "bidirectional"))
      (node (ref "C18") (pin "P$2") (pinfunction "P$2_P$2") (pintype "bidirectional"))
      (node (ref "C19") (pin "P$2") (pinfunction "P$2_P$2") (pintype "bidirectional"))
      (node (ref "C2") (pin "P$2") (pinfunction "P$2_P$2") (pintype "bidirectional"))
      (node (ref "C20") (pin "P$2") (pinfunction "P$2_P$2") (pintype "bidirectional"))
      (node (ref "C22") (pin "P$2") (pinfunction "P$2_P$2") (pintype "bidirectional"))
      (node (ref "C23") (pin "P$2") (pinfunction "P$2_P$2") (pintype "bidirectional"))
      (node (ref "C24") (pin "P$2") (pinfunction "P$2_P$2") (pintype "bidirectional"))
      (node (ref "C25") (pin "P$2") (pinfunction "P$2_P$2") (pintype "bidirectional"))
      (node (ref "C26") (pin "P$2") (pinfunction "P$2_P$2") (pintype "bidirectional"))
      (node (ref "C27") (pin "P$2") (pinfunction "P$2_P$2") (pintype "bidirectional"))
      (node (ref "C3") (pin "P$2") (pinfunction "P$2_P$2") (pintype "bidirectional"))
      (node (ref "C4") (pin "2") (pinfunction "P$2_2") (pintype "bidirectional"))
      (node (ref "C5") (pin "P$2") (pinfunction "P$2_P$2") (pintype "bidirectional"))
      (node (ref "C6") (pin "-") (pinfunction "CA_-") (pintype "bidirectional"))
      (node (ref "C7") (pin "P$2") (pinfunction "P$2_P$2") (pintype "bidirectional"))
      (node (ref "C8") (pin "P$2") (pinfunction "P$2_P$2") (pintype "bidirectional"))
      (node (ref "C9") (pin "P$2") (pinfunction "P$2_P$2") (pintype "bidirectional"))
      (node (ref "D1") (pin "A") (pinfunction "A_A") (pintype "bidirectional"))
      (node (ref "D10") (pin "2") (pinfunction "GND_2") (pintype "bidirectional"))
      (node (ref "D11") (pin "2") (pinfunction "GND_2") (pintype "bidirectional"))
      (node (ref "D12") (pin "2") (pinfunction "GND_2") (pintype "bidirectional"))
      (node (ref "D13") (pin "2") (pinfunction "GND_2") (pintype "bidirectional"))
      (node (ref "D14") (pin "2") (pinfunction "GND_2") (pintype "bidirectional"))
      (node (ref "D2") (pin "C") (pinfunction "CA_C") (pintype "bidirectional"))
      (node (ref "D3") (pin "A") (pinfunction "A_A") (pintype "passive"))
      (node (ref "D4") (pin "1") (pinfunction "1_1") (pintype "bidirectional"))
      (node (ref "D7") (pin "2") (pinfunction "GND_2") (pintype "bidirectional"))
      (node (ref "D8") (pin "2") (pinfunction "GND_2") (pintype "bidirectional"))
      (node (ref "D9") (pin "2") (pinfunction "GND_2") (pintype "bidirectional"))
      (node (ref "J1") (pin "3-BAR") (pinfunction "S_3-BAR") (pintype "passive"))
      (node (ref "J1") (pin "4-BAR") (pinfunction "S_4-BAR") (pintype "passive"))
      (node (ref "J10") (pin "A1_B12") (pinfunction "GND_A1_B12") (pintype "bidirectional"))
      (node (ref "J10") (pin "B1_A12") (pinfunction "GND_B1_A12") (pintype "bidirectional"))
      (node (ref "J10") (pin "SHIELD0") (pinfunction "GND_SHIELD0") (pintype "bidirectional"))
      (node (ref "J10") (pin "SHIELD1") (pinfunction "GND_SHIELD1") (pintype "bidirectional"))
      (node (ref "J10") (pin "SHIELD2") (pinfunction "GND_SHIELD2") (pintype "bidirectional"))
      (node (ref "J10") (pin "SHIELD3") (pinfunction "GND_SHIELD3") (pintype "bidirectional"))
      (node (ref "J2") (pin "2") (pinfunction "S_2") (pintype "passive"))
      (node (ref "J3") (pin "3-BAR") (pinfunction "S_3-BAR") (pintype "passive"))
      (node (ref "J3") (pin "4-BAR") (pinfunction "S_4-BAR") (pintype "passive"))
      (node (ref "J4") (pin "6") (pinfunction "6_6") (pintype "bidirectional"))
      (node (ref "J4") (pin "BODY1") (pinfunction "BODY_BODY1") (pintype "bidirectional"))
      (node (ref "J4") (pin "BODY2") (pinfunction "BODY_BODY2") (pintype "bidirectional"))
      (node (ref "J4") (pin "BODY3") (pinfunction "BODY_BODY3") (pintype "bidirectional"))
      (node (ref "J4") (pin "BODY4") (pinfunction "BODY_BODY4") (pintype "bidirectional"))
      (node (ref "J5") (pin "P$2") (pinfunction "S_P$2") (pintype "passive"))
      (node (ref "J6") (pin "P$3") (pinfunction "S_P$3") (pintype "passive"))
      (node (ref "J8") (pin "P$1") (pinfunction "S_P$1") (pintype "passive"))
      (node (ref "J9") (pin "P$2") (pinfunction "S_P$2") (pintype "passive"))
      (node (ref "M1") (pin "12") (pinfunction "GND_12") (pintype "bidirectional"))
      (node (ref "Q1") (pin "P$2") (pinfunction "EM2_P$2") (pintype "bidirectional"))
      (node (ref "Q2") (pin "P$2") (pinfunction "EM2_P$2") (pintype "bidirectional"))
      (node (ref "Q3") (pin "P$2") (pinfunction "EM2_P$2") (pintype "bidirectional"))
      (node (ref "Q4") (pin "P$2") (pinfunction "EM2_P$2") (pintype "bidirectional"))
      (node (ref "R16") (pin "P$1") (pinfunction "P$1_P$1") (pintype "bidirectional"))
      (node (ref "R2") (pin "P$1") (pinfunction "P$1_P$1") (pintype "bidirectional"))
      (node (ref "R25") (pin "P$1") (pinfunction "P$1_P$1") (pintype "bidirectional"))
      (node (ref "R31") (pin "P$1") (pinfunction "P$1_P$1") (pintype "bidirectional"))
      (node (ref "R33") (pin "P$1") (pinfunction "P$1_P$1") (pintype "bidirectional"))
      (node (ref "R34") (pin "P$1") (pinfunction "P$1_P$1") (pintype "bidirectional"))
      (node (ref "R7") (pin "P$1") (pinfunction "P$1_P$1") (pintype "bidirectional"))
      (node (ref "R9") (pin "P$1") (pinfunction "P$1_P$1") (pintype "bidirectional"))
      (node (ref "SW1") (pin "3") (pinfunction "3_3") (pintype "passive"))
      (node (ref "SW1") (pin "4") (pinfunction "4_4") (pintype "passive"))
      (node (ref "TC1") (pin "3") (pinfunction "S_3") (pintype "passive"))
      (node (ref "TC1") (pin "9") (pinfunction "S_9") (pintype "passive"))
      (node (ref "U1") (pin "2") (pinfunction "GND_2") (pintype "bidirectional"))
      (node (ref "U1") (pin "4") (pinfunction "SHDN_4") (pintype "bidirectional"))
      (node (ref "U1") (pin "6") (pinfunction "GND_6") (pintype "bidirectional"))
      (node (ref "U1") (pin "7") (pinfunction "GND_7") (pintype "bidirectional"))
      (node (ref "U10") (pin "16") (pinfunction "VSS_16") (pintype "bidirectional"))
      (node (ref "U10") (pin "32") (pinfunction "VSS_32") (pintype "bidirectional"))
      (node (ref "U10") (pin "58") (pinfunction "VSS_58") (pintype "bidirectional"))
      (node (ref "U10") (pin "83") (pinfunction "VSS_83") (pintype "bidirectional"))
      (node (ref "U2") (pin "1") (pinfunction "GND_1") (pintype "bidirectional"))
      (node (ref "U2") (pin "10") (pinfunction "GND_10") (pintype "bidirectional"))
      (node (ref "U2") (pin "13") (pinfunction "GND_13") (pintype "bidirectional"))
      (node (ref "U2") (pin "16") (pinfunction "ADDR_16") (pintype "bidirectional"))
      (node (ref "U2") (pin "17") (pinfunction "GND_17") (pintype "bidirectional"))
      (node (ref "U2") (pin "18") (pinfunction "GND_18") (pintype "bidirectional"))
      (node (ref "U2") (pin "3") (pinfunction "GND_3") (pintype "bidirectional"))
      (node (ref "U2") (pin "5") (pinfunction "GND_5") (pintype "bidirectional"))
      (node (ref "U2") (pin "6") (pinfunction "GND_6") (pintype "bidirectional"))
      (node (ref "U2") (pin "7") (pinfunction "GND_7") (pintype "bidirectional"))
      (node (ref "U2") (pin "9") (pinfunction "GND_9") (pintype "bidirectional"))
      (node (ref "U2") (pin "EXP") (pinfunction "EP_EXP") (pintype "bidirectional"))
      (node (ref "U3") (pin "4") (pinfunction "GND_4") (pintype "power_in"))
      (node (ref "U4") (pin "1") (pinfunction "GND_1") (pintype "bidirectional"))
      (node (ref "U4") (pin "10") (pinfunction "GND_10") (pintype "bidirectional"))
      (node (ref "U4") (pin "13") (pinfunction "GND_13") (pintype "bidirectional"))
      (node (ref "U4") (pin "17") (pinfunction "GND_17") (pintype "bidirectional"))
      (node (ref "U4") (pin "18") (pinfunction "GND_18") (pintype "bidirectional"))
      (node (ref "U4") (pin "3") (pinfunction "GND_3") (pintype "bidirectional"))
      (node (ref "U4") (pin "5") (pinfunction "GND_5") (pintype "bidirectional"))
      (node (ref "U4") (pin "6") (pinfunction "GND_6") (pintype "bidirectional"))
      (node (ref "U4") (pin "7") (pinfunction "GND_7") (pintype "bidirectional"))
      (node (ref "U4") (pin "9") (pinfunction "GND_9") (pintype "bidirectional"))
      (node (ref "U4") (pin "EXP") (pinfunction "EP_EXP") (pintype "bidirectional"))
      (node (ref "U5") (pin "3") (pinfunction "GND_3") (pintype "bidirectional"))
      (node (ref "U6") (pin "2") (pinfunction "GND_2") (pintype "bidirectional"))
      (node (ref "U6") (pin "PAD") (pinfunction "GND_PAD") (pintype "bidirectional"))
      (node (ref "U7") (pin "11") (pinfunction "VSYNC_11") (pintype "bidirectional"))
      (node (ref "U7") (pin "12") (pinfunction "HSYNC_12") (pintype "bidirectional"))
      (node (ref "U7") (pin "13") (pinfunction "DOTCLK_13") (pintype "bidirectional"))
      (node (ref "U7") (pin "14") (pinfunction "DE_14") (pintype "bidirectional"))
      (node (ref "U7") (pin "15") (pinfunction "DB17_15") (pintype "bidirectional"))
      (node (ref "U7") (pin "16") (pinfunction "DB16_16") (pintype "bidirectional"))
      (node (ref "U7") (pin "17") (pinfunction "DB15_17") (pintype "bidirectional"))
      (node (ref "U7") (pin "18") (pinfunction "DB14_18") (pintype "bidirectional"))
      (node (ref "U7") (pin "19") (pinfunction "DB13_19") (pintype "bidirectional"))
      (node (ref "U7") (pin "20") (pinfunction "DB12_20") (pintype "bidirectional"))
      (node (ref "U7") (pin "21") (pinfunction "DB11_21") (pintype "bidirectional"))
      (node (ref "U7") (pin "22") (pinfunction "DB10_22") (pintype "bidirectional"))
      (node (ref "U7") (pin "23") (pinfunction "DB9_23") (pintype "bidirectional"))
      (node (ref "U7") (pin "24") (pinfunction "DB8_24") (pintype "bidirectional"))
      (node (ref "U7") (pin "25") (pinfunction "DB7_25") (pintype "bidirectional"))
      (node (ref "U7") (pin "26") (pinfunction "DB6_26") (pintype "bidirectional"))
      (node (ref "U7") (pin "27") (pinfunction "DB5_27") (pintype "bidirectional"))
      (node (ref "U7") (pin "28") (pinfunction "DB4_28") (pintype "bidirectional"))
      (node (ref "U7") (pin "29") (pinfunction "DB3_29") (pintype "bidirectional"))
      (node (ref "U7") (pin "30") (pinfunction "DB2_30") (pintype "bidirectional"))
      (node (ref "U7") (pin "31") (pinfunction "DB1_31") (pintype "bidirectional"))
      (node (ref "U7") (pin "32") (pinfunction "DB0_32") (pintype "bidirectional"))
      (node (ref "U7") (pin "39") (pinfunction "TE_39") (pintype "bidirectional"))
      (node (ref "U7") (pin "43") (pinfunction "GND_43") (pintype "bidirectional"))
      (node (ref "U7") (pin "48") (pinfunction "GND_48") (pintype "bidirectional"))
      (node (ref "U7") (pin "49") (pinfunction "GND_49") (pintype "bidirectional"))
      (node (ref "U7") (pin "50") (pinfunction "GND_50") (pintype "bidirectional"))
      (node (ref "U8") (pin "3") (pinfunction "GND_3") (pintype "bidirectional"))
      (node (ref "U9") (pin "3") (pinfunction "GND_3") (pintype "bidirectional"))
    )
    (net (code "14") (name "I2C0-SCL-SENS") (class "Default")
      (node (ref "R13") (pin "P$1") (pinfunction "P$1_P$1") (pintype "bidirectional"))
      (node (ref "U10") (pin "53") (pinfunction "PD7_53") (pintype "bidirectional"))
      (node (ref "U2") (pin "19") (pinfunction "SCL_19") (pintype "bidirectional"))
      (node (ref "U4") (pin "19") (pinfunction "SCL_19") (pintype "bidirectional"))
    )
    (net (code "15") (name "I2C0-SDA-SENS") (class "Default")
      (node (ref "R12") (pin "P$1") (pinfunction "P$1_P$1") (pintype "bidirectional"))
      (node (ref "U10") (pin "52") (pinfunction "PD6_52") (pintype "bidirectional"))
      (node (ref "U2") (pin "20") (pinfunction "SDA_20") (pintype "bidirectional"))
      (node (ref "U4") (pin "20") (pinfunction "SDA_20") (pintype "bidirectional"))
    )
    (net (code "16") (name "I2C1-SCL-TTFT") (class "Default")
      (node (ref "R15") (pin "P$1") (pinfunction "P$1_P$1") (pintype "bidirectional"))
      (node (ref "U10") (pin "40") (pinfunction "PB12_40") (pintype "bidirectional"))
      (node (ref "U7") (pin "44") (pinfunction "X+/SCL_44") (pintype "bidirectional"))
    )
    (net (code "17") (name "I2C1-SDA-TTFT") (class "Default")
      (node (ref "R14") (pin "P$1") (pinfunction "P$1_P$1") (pintype "bidirectional"))
      (node (ref "U10") (pin "39") (pinfunction "PB11_39") (pintype "bidirectional"))
      (node (ref "U7") (pin "45") (pinfunction "Y+/SDA_45") (pintype "bidirectional"))
    )
    (net (code "18") (name "MAIN_HFXTAL_N") (class "Default")
      (node (ref "U10") (pin "42") (pinfunction "PB13_42") (pintype "bidirectional"))
      (node (ref "Y1") (pin "1") (pinfunction "1_1") (pintype "passive"))
    )
    (net (code "19") (name "MAIN_HFXTAL_P") (class "Default")
      (node (ref "U10") (pin "43") (pinfunction "PB14_43") (pintype "bidirectional"))
      (node (ref "Y1") (pin "2") (pinfunction "2_2") (pintype "passive"))
    )
    (net (code "20") (name "MAIN_LFXTAL_N") (class "Default")
      (node (ref "U10") (pin "25") (pinfunction "PB8_25") (pintype "bidirectional"))
      (node (ref "Y2") (pin "4") (pinfunction "2_4") (pintype "passive"))
    )
    (net (code "21") (name "MAIN_LFXTAL_P") (class "Default")
      (node (ref "U10") (pin "24") (pinfunction "PB7_24") (pintype "bidirectional"))
      (node (ref "Y2") (pin "1") (pinfunction "1_1") (pintype "passive"))
    )
    (net (code "22") (name "Net-(B1-A)") (class "Default")
      (node (ref "B1") (pin "1") (pinfunction "A_1") (pintype "bidirectional"))
      (node (ref "R23") (pin "P$1") (pinfunction "P$1_P$1") (pintype "bidirectional"))
    )
    (net (code "23") (name "Net-(B1-B)") (class "Default")
      (node (ref "B1") (pin "2") (pinfunction "B_2") (pintype "bidirectional"))
      (node (ref "Q1") (pin "P$3") (pinfunction "C03_P$3") (pintype "bidirectional"))
      (node (ref "R21") (pin "P$1") (pinfunction "P$1_P$1") (pintype "bidirectional"))
    )
    (net (code "24") (name "Net-(D2-AN)") (class "Default")
      (node (ref "D2") (pin "A") (pinfunction "AN_A") (pintype "bidirectional"))
      (node (ref "R10") (pin "P$2") (pinfunction "P$2_P$2") (pintype "bidirectional"))
    )
    (net (code "25") (name "Net-(D5-AN)") (class "Default")
      (node (ref "D5") (pin "A") (pinfunction "AN_A") (pintype "bidirectional"))
      (node (ref "R24") (pin "P$2") (pinfunction "P$2_P$2") (pintype "bidirectional"))
    )
    (net (code "26") (name "Net-(D5-CA)") (class "Default")
      (node (ref "D5") (pin "C") (pinfunction "CA_C") (pintype "bidirectional"))
      (node (ref "U6") (pin "13") (pinfunction "GPIO1-RXT_13") (pintype "bidirectional"))
    )
    (net (code "27") (name "Net-(D6-AN)") (class "Default")
      (node (ref "D6") (pin "A") (pinfunction "AN_A") (pintype "bidirectional"))
      (node (ref "R26") (pin "P$2") (pinfunction "P$2_P$2") (pintype "bidirectional"))
    )
    (net (code "28") (name "Net-(D6-CA)") (class "Default")
      (node (ref "D6") (pin "C") (pinfunction "CA_C") (pintype "bidirectional"))
      (node (ref "U6") (pin "14") (pinfunction "GPIO0-TXT_14") (pintype "bidirectional"))
    )
    (net (code "29") (name "Net-(D7-CLKI)") (class "Default")
      (node (ref "D7") (pin "4") (pinfunction "CLKI_4") (pintype "bidirectional"))
      (node (ref "U9") (pin "4") (pinfunction "Y_4") (pintype "output"))
    )
    (net (code "30") (name "Net-(D7-CLKO)") (class "Default")
      (node (ref "D7") (pin "6") (pinfunction "CLKO_6") (pintype "bidirectional"))
      (node (ref "D8") (pin "4") (pinfunction "CLKI_4") (pintype "bidirectional"))
    )
    (net (code "31") (name "Net-(D7-SDI)") (class "Default")
      (node (ref "D7") (pin "3") (pinfunction "SDI_3") (pintype "bidirectional"))
      (node (ref "U8") (pin "4") (pinfunction "Y_4") (pintype "output"))
    )
    (net (code "32") (name "Net-(D7-SDO)") (class "Default")
      (node (ref "D7") (pin "1") (pinfunction "SDO_1") (pintype "bidirectional"))
      (node (ref "D8") (pin "3") (pinfunction "SDI_3") (pintype "bidirectional"))
    )
    (net (code "33") (name "Net-(D8-CLKO)") (class "Default")
      (node (ref "D8") (pin "6") (pinfunction "CLKO_6") (pintype "bidirectional"))
      (node (ref "D9") (pin "4") (pinfunction "CLKI_4") (pintype "bidirectional"))
    )
    (net (code "34") (name "Net-(D8-SDO)") (class "Default")
      (node (ref "D8") (pin "1") (pinfunction "SDO_1") (pintype "bidirectional"))
      (node (ref "D9") (pin "3") (pinfunction "SDI_3") (pintype "bidirectional"))
    )
    (net (code "35") (name "Net-(D10-CLKI)") (class "Default")
      (node (ref "D10") (pin "4") (pinfunction "CLKI_4") (pintype "bidirectional"))
      (node (ref "D9") (pin "6") (pinfunction "CLKO_6") (pintype "bidirectional"))
    )
    (net (code "36") (name "Net-(D10-CLKO)") (class "Default")
      (node (ref "D10") (pin "6") (pinfunction "CLKO_6") (pintype "bidirectional"))
      (node (ref "D11") (pin "4") (pinfunction "CLKI_4") (pintype "bidirectional"))
    )
    (net (code "37") (name "Net-(D10-SDI)") (class "Default")
      (node (ref "D10") (pin "3") (pinfunction "SDI_3") (pintype "bidirectional"))
      (node (ref "D9") (pin "1") (pinfunction "SDO_1") (pintype "bidirectional"))
    )
    (net (code "38") (name "Net-(D10-SDO)") (class "Default")
      (node (ref "D10") (pin "1") (pinfunction "SDO_1") (pintype "bidirectional"))
      (node (ref "D11") (pin "3") (pinfunction "SDI_3") (pintype "bidirectional"))
    )
    (net (code "39") (name "Net-(D11-CLKO)") (class "Default")
      (node (ref "D11") (pin "6") (pinfunction "CLKO_6") (pintype "bidirectional"))
      (node (ref "D12") (pin "4") (pinfunction "CLKI_4") (pintype "bidirectional"))
    )
    (net (code "40") (name "Net-(D11-SDO)") (class "Default")
      (node (ref "D11") (pin "1") (pinfunction "SDO_1") (pintype "bidirectional"))
      (node (ref "D12") (pin "3") (pinfunction "SDI_3") (pintype "bidirectional"))
    )
    (net (code "41") (name "Net-(D12-CLKO)") (class "Default")
      (node (ref "D12") (pin "6") (pinfunction "CLKO_6") (pintype "bidirectional"))
      (node (ref "D13") (pin "4") (pinfunction "CLKI_4") (pintype "bidirectional"))
    )
    (net (code "42") (name "Net-(D12-SDO)") (class "Default")
      (node (ref "D12") (pin "1") (pinfunction "SDO_1") (pintype "bidirectional"))
      (node (ref "D13") (pin "3") (pinfunction "SDI_3") (pintype "bidirectional"))
    )
    (net (code "43") (name "Net-(D13-CLKO)") (class "Default")
      (node (ref "D13") (pin "6") (pinfunction "CLKO_6") (pintype "bidirectional"))
      (node (ref "D14") (pin "4") (pinfunction "CLKI_4") (pintype "bidirectional"))
    )
    (net (code "44") (name "Net-(D13-SDO)") (class "Default")
      (node (ref "D13") (pin "1") (pinfunction "SDO_1") (pintype "bidirectional"))
      (node (ref "D14") (pin "3") (pinfunction "SDI_3") (pintype "bidirectional"))
    )
    (net (code "45") (name "Net-(GND-2)") (class "Default")
      (node (ref "GND") (pin "P$2") (pinfunction "2_P$2") (pintype "passive"))
      (node (ref "J5") (pin "P$1") (pinfunction "S_P$1") (pintype "passive"))
    )
    (net (code "46") (name "Net-(J1B-S)") (class "Default")
      (node (ref "J1") (pin "1-T+") (pinfunction "S_1-T+") (pintype "passive"))
      (node (ref "U2") (pin "2") (pinfunction "VIN+_2") (pintype "bidirectional"))
    )
    (net (code "47") (name "Net-(J1C-S)") (class "Default")
      (node (ref "J1") (pin "2-T-") (pinfunction "S_2-T-") (pintype "passive"))
      (node (ref "U2") (pin "4") (pinfunction "VIN-_4") (pintype "bidirectional"))
    )
    (net (code "48") (name "Net-(J2A-S)") (class "Default")
      (node (ref "J2") (pin "1") (pinfunction "S_1") (pintype "passive"))
      (node (ref "R4") (pin "P$1") (pinfunction "P$1_P$1") (pintype "bidirectional"))
      (node (ref "R5") (pin "P$1") (pinfunction "P$1_P$1") (pintype "bidirectional"))
    )
    (net (code "49") (name "Net-(J3B-S)") (class "Default")
      (node (ref "J3") (pin "1-T+") (pinfunction "S_1-T+") (pintype "passive"))
      (node (ref "U4") (pin "2") (pinfunction "VIN+_2") (pintype "bidirectional"))
    )
    (net (code "50") (name "Net-(J3C-S)") (class "Default")
      (node (ref "J3") (pin "2-T-") (pinfunction "S_2-T-") (pintype "passive"))
      (node (ref "U4") (pin "4") (pinfunction "VIN-_4") (pintype "bidirectional"))
    )
    (net (code "51") (name "Net-(J6A-S)") (class "Default")
      (node (ref "J6") (pin "P$1") (pinfunction "S_P$1") (pintype "passive"))
      (node (ref "U5") (pin "4") (pinfunction "Y_4") (pintype "output"))
    )
    (net (code "52") (name "Net-(J7B-S)") (class "Default")
      (node (ref "J7") (pin "4") (pinfunction "S_4") (pintype "passive"))
      (node (ref "Q2") (pin "P$3") (pinfunction "C03_P$3") (pintype "bidirectional"))
      (node (ref "R22") (pin "P$1") (pinfunction "P$1_P$1") (pintype "bidirectional"))
    )
    (net (code "53") (name "Net-(J7C-S)") (class "Default")
      (node (ref "J7") (pin "1") (pinfunction "S_1") (pintype "passive"))
      (node (ref "Q3") (pin "P$3") (pinfunction "C03_P$3") (pintype "bidirectional"))
    )
    (net (code "54") (name "Net-(J7D-S)") (class "Default")
      (node (ref "J7") (pin "3") (pinfunction "S_3") (pintype "passive"))
      (node (ref "R20") (pin "P$2") (pinfunction "P$2_P$2") (pintype "bidirectional"))
    )
    (net (code "55") (name "Net-(J10-CC1)") (class "Default")
      (node (ref "J10") (pin "A5") (pinfunction "CC1_A5") (pintype "bidirectional"))
      (node (ref "R33") (pin "P$2") (pinfunction "P$2_P$2") (pintype "bidirectional"))
    )
    (net (code "56") (name "Net-(J10-CC2)") (class "Default")
      (node (ref "J10") (pin "B5") (pinfunction "CC2_B5") (pintype "bidirectional"))
      (node (ref "R34") (pin "P$2") (pinfunction "P$2_P$2") (pintype "bidirectional"))
    )
    (net (code "57") (name "Net-(L1-P$1)") (class "Default")
      (node (ref "D1") (pin "C") (pinfunction "C_C") (pintype "bidirectional"))
      (node (ref "L1") (pin "1") (pinfunction "P$1_1") (pintype "bidirectional"))
      (node (ref "U1") (pin "8") (pinfunction "SW_8") (pintype "bidirectional"))
    )
    (net (code "58") (name "Net-(M1-PIO1)") (class "Default")
      (node (ref "M1") (pin "15") (pinfunction "PIO1_15") (pintype "bidirectional"))
      (node (ref "R10") (pin "P$1") (pinfunction "P$1_P$1") (pintype "bidirectional"))
    )
    (net (code "59") (name "Net-(Q1-BA1)") (class "Default")
      (node (ref "Q1") (pin "P$1") (pinfunction "BA1_P$1") (pintype "bidirectional"))
      (node (ref "R17") (pin "P$2") (pinfunction "P$2_P$2") (pintype "bidirectional"))
    )
    (net (code "60") (name "Net-(Q2-BA1)") (class "Default")
      (node (ref "Q2") (pin "P$1") (pinfunction "BA1_P$1") (pintype "bidirectional"))
      (node (ref "R18") (pin "P$2") (pinfunction "P$2_P$2") (pintype "bidirectional"))
    )
    (net (code "61") (name "Net-(Q3-BA1)") (class "Default")
      (node (ref "Q3") (pin "P$1") (pinfunction "BA1_P$1") (pintype "bidirectional"))
      (node (ref "R19") (pin "P$2") (pinfunction "P$2_P$2") (pintype "bidirectional"))
    )
    (net (code "62") (name "Net-(Q4-BA1)") (class "Default")
      (node (ref "Q4") (pin "P$1") (pinfunction "BA1_P$1") (pintype "bidirectional"))
      (node (ref "R27") (pin "P$2") (pinfunction "P$2_P$2") (pintype "bidirectional"))
    )
    (net (code "63") (name "Net-(Q4-C03)") (class "Default")
      (node (ref "Q4") (pin "P$3") (pinfunction "C03_P$3") (pintype "bidirectional"))
      (node (ref "R29") (pin "P$1") (pinfunction "P$1_P$1") (pintype "bidirectional"))
      (node (ref "R32") (pin "P$1") (pinfunction "P$1_P$1") (pintype "bidirectional"))
    )
    (net (code "64") (name "Net-(R29-PadP$2)") (class "Default")
      (node (ref "R29") (pin "P$2") (pinfunction "P$2_P$2") (pintype "bidirectional"))
      (node (ref "U7") (pin "2") (pinfunction "LEDK_2") (pintype "bidirectional"))
    )
    (net (code "65") (name "Net-(R32-PadP$2)") (class "Default")
      (node (ref "R32") (pin "P$2") (pinfunction "P$2_P$2") (pintype "bidirectional"))
      (node (ref "U7") (pin "3") (pinfunction "LEDK_3") (pintype "bidirectional"))
    )
    (net (code "66") (name "Net-(U1-FB)") (class "Default")
      (node (ref "R6") (pin "P$1") (pinfunction "P$1_P$1") (pintype "bidirectional"))
      (node (ref "R7") (pin "P$2") (pinfunction "P$2_P$2") (pintype "bidirectional"))
      (node (ref "U1") (pin "1") (pinfunction "FB_1") (pintype "bidirectional"))
    )
    (net (code "67") (name "Net-(U1-ISET)") (class "Default")
      (node (ref "R1") (pin "P$1") (pinfunction "P$1_P$1") (pintype "bidirectional"))
      (node (ref "R2") (pin "P$2") (pinfunction "P$2_P$2") (pintype "bidirectional"))
      (node (ref "U1") (pin "3") (pinfunction "ISET_3") (pintype "bidirectional"))
    )
    (net (code "68") (name "Net-(U10-DECOUPLE)") (class "Default")
      (node (ref "C27") (pin "P$1") (pinfunction "P$1_P$1") (pintype "bidirectional"))
      (node (ref "U10") (pin "59") (pinfunction "DECOUPLE_59") (pintype "bidirectional"))
    )
    (net (code "69") (name "PRS-CH11-SSR-OUT") (class "Default")
      (node (ref "J9") (pin "P$1") (pinfunction "S_P$1") (pintype "passive"))
      (node (ref "U10") (pin "51") (pinfunction "PD5_51") (pintype "bidirectional"))
    )
    (net (code "70") (name "QSPI_CLK") (class "Default")
      (node (ref "U10") (pin "84") (pinfunction "PF6_84") (pintype "bidirectional"))
      (node (ref "U3") (pin "6") (pinfunction "SCK_6") (pintype "input"))
    )
    (net (code "71") (name "QSPI_CS0") (class "Default")
      (node (ref "R3") (pin "P$1") (pinfunction "P$1_P$1") (pintype "bidirectional"))
      (node (ref "U10") (pin "85") (pinfunction "PF7_85") (pintype "bidirectional"))
      (node (ref "U3") (pin "1") (pinfunction "~{CS}_1") (pintype "input"))
    )
    (net (code "72") (name "QSPI_D0") (class "Default")
      (node (ref "U10") (pin "88") (pinfunction "PD9_88") (pintype "bidirectional"))
      (node (ref "U3") (pin "5") (pinfunction "MOSI/IO0_5") (pintype "input"))
    )
    (net (code "73") (name "QSPI_D1") (class "Default")
      (node (ref "U10") (pin "89") (pinfunction "PD10_89") (pintype "bidirectional"))
      (node (ref "U3") (pin "2") (pinfunction "MISO/IO1_2") (pintype "output"))
    )
    (net (code "74") (name "QSPI_D2") (class "Default")
      (node (ref "U10") (pin "90") (pinfunction "PD11_90") (pintype "bidirectional"))
      (node (ref "U3") (pin "3") (pinfunction "~{WP}/IO2_3") (pintype "input"))
    )
    (net (code "75") (name "QSPI_D3") (class "Default")
      (node (ref "U10") (pin "91") (pinfunction "PD12_91") (pintype "bidirectional"))
      (node (ref "U3") (pin "7") (pinfunction "~{HOLD}/IO3_7") (pintype "input"))
    )
    (net (code "76") (name "SDIO-CD") (class "Default")
      (node (ref "J4") (pin "9") (pinfunction "CD_9") (pintype "bidirectional"))
      (node (ref "R11") (pin "P$1") (pinfunction "P$1_P$1") (pintype "bidirectional"))
      (node (ref "U10") (pin "86") (pinfunction "PF8_86") (pintype "bidirectional"))
    )
    (net (code "77") (name "SDIO-CLK") (class "Default")
      (node (ref "J4") (pin "5") (pinfunction "5_5") (pintype "bidirectional"))
      (node (ref "U10") (pin "97") (pinfunction "PE13_97") (pintype "bidirectional"))
    )
    (net (code "78") (name "SDIO-CMD") (class "Default")
      (node (ref "J4") (pin "3") (pinfunction "3_3") (pintype "bidirectional"))
      (node (ref "U10") (pin "96") (pinfunction "PE12_96") (pintype "bidirectional"))
    )
    (net (code "79") (name "SDIO-DAT0") (class "Default")
      (node (ref "J4") (pin "7") (pinfunction "7_7") (pintype "bidirectional"))
      (node (ref "U10") (pin "95") (pinfunction "PE11_95") (pintype "bidirectional"))
    )
    (net (code "80") (name "SDIO-DAT1") (class "Default")
      (node (ref "J4") (pin "8") (pinfunction "8_8") (pintype "bidirectional"))
      (node (ref "U10") (pin "94") (pinfunction "PE10_94") (pintype "bidirectional"))
    )
    (net (code "81") (name "SDIO-DAT2") (class "Default")
      (node (ref "J4") (pin "1") (pinfunction "1_1") (pintype "bidirectional"))
      (node (ref "U10") (pin "93") (pinfunction "PE9_93") (pintype "bidirectional"))
    )
    (net (code "82") (name "SDIO-DAT3") (class "Default")
      (node (ref "J4") (pin "2") (pinfunction "2_2") (pintype "bidirectional"))
      (node (ref "U10") (pin "92") (pinfunction "PE8_92") (pintype "bidirectional"))
    )
    (net (code "83") (name "SWCLK") (class "Default")
      (node (ref "TC1") (pin "4") (pinfunction "S_4") (pintype "passive"))
      (node (ref "U10") (pin "76") (pinfunction "PF0_76") (pintype "bidirectional"))
    )
    (net (code "84") (name "SWDIO") (class "Default")
      (node (ref "TC1") (pin "2") (pinfunction "S_2") (pintype "passive"))
      (node (ref "U10") (pin "77") (pinfunction "PF1_77") (pintype "bidirectional"))
    )
    (net (code "85") (name "SWO") (class "Default")
      (node (ref "TC1") (pin "6") (pinfunction "S_6") (pintype "passive"))
      (node (ref "U10") (pin "78") (pinfunction "PF2_78") (pintype "bidirectional"))
    )
    (net (code "86") (name "TFT-DC") (class "Default")
      (node (ref "U10") (pin "19") (pinfunction "PC1_19") (pintype "bidirectional"))
      (node (ref "U7") (pin "37") (pinfunction "D/~{C}_37") (pintype "bidirectional"))
    )
    (net (code "87") (name "TIM0-CC0-BUZZ") (class "Default")
      (node (ref "U10") (pin "27") (pinfunction "PA8_27") (pintype "bidirectional"))
    )
    (net (code "88") (name "TIM0-CC2-BUZZ") (class "Default")
      (node (ref "R17") (pin "P$1") (pinfunction "P$1_P$1") (pintype "bidirectional"))
    )
    (net (code "89") (name "TIM1-CC0-TFT-BL") (class "Default")
      (node (ref "R25") (pin "P$2") (pinfunction "P$2_P$2") (pintype "bidirectional"))
      (node (ref "R27") (pin "P$1") (pinfunction "P$1_P$1") (pintype "bidirectional"))
      (node (ref "U10") (pin "9") (pinfunction "PB0_9") (pintype "bidirectional"))
    )
    (net (code "90") (name "TIM2-CC2FAN0-SNSE") (class "Default")
      (node (ref "R16") (pin "P$2") (pinfunction "P$2_P$2") (pintype "bidirectional"))
      (node (ref "R20") (pin "P$1") (pinfunction "P$1_P$1") (pintype "bidirectional"))
      (node (ref "U10") (pin "70") (pinfunction "PC10_70") (pintype "bidirectional"))
    )
    (net (code "91") (name "TIM5-CC0-FAN0-GND") (class "Default")
      (node (ref "R19") (pin "P$1") (pinfunction "P$1_P$1") (pintype "bidirectional"))
      (node (ref "U10") (pin "68") (pinfunction "PC8_68") (pintype "bidirectional"))
    )
    (net (code "92") (name "TIM5-CC1-FAN0-CTRL") (class "Default")
      (node (ref "R18") (pin "P$1") (pinfunction "P$1_P$1") (pintype "bidirectional"))
      (node (ref "U10") (pin "69") (pinfunction "PC9_69") (pintype "bidirectional"))
    )
    (net (code "93") (name "U0RX-USB-TX") (class "Default")
      (node (ref "U10") (pin "5") (pinfunction "PA4_5") (pintype "bidirectional"))
      (node (ref "U6") (pin "21") (pinfunction "TXD_21") (pintype "bidirectional"))
    )
    (net (code "94") (name "U0TX-USB-RX") (class "Default")
      (node (ref "U10") (pin "4") (pinfunction "PA3_4") (pintype "bidirectional"))
      (node (ref "U6") (pin "20") (pinfunction "RXD_20") (pintype "bidirectional"))
    )
    (net (code "95") (name "U1RX-BLE-TX") (class "Default")
      (node (ref "M1") (pin "2") (pinfunction "TX_2") (pintype "bidirectional"))
      (node (ref "U10") (pin "63") (pinfunction "PE3_63") (pintype "bidirectional"))
    )
    (net (code "96") (name "U1TX-BLE-RX") (class "Default")
      (node (ref "M1") (pin "4") (pinfunction "RX_4") (pintype "bidirectional"))
      (node (ref "U10") (pin "62") (pinfunction "PE2_62") (pintype "bidirectional"))
    )
    (net (code "97") (name "UART_VBUS") (class "Default")
      (node (ref "R30") (pin "P$1") (pinfunction "P$1_P$1") (pintype "bidirectional"))
      (node (ref "R31") (pin "P$2") (pinfunction "P$2_P$2") (pintype "bidirectional"))
      (node (ref "U6") (pin "8") (pinfunction "VBUS_8") (pintype "bidirectional"))
    )
    (net (code "98") (name "US0-LED-MOSI") (class "Default")
      (node (ref "U10") (pin "67") (pinfunction "PE7_67") (pintype "bidirectional"))
      (node (ref "U8") (pin "2") (pinfunction "A_2") (pintype "input"))
    )
    (net (code "99") (name "US0-LED-SCK") (class "Default")
      (node (ref "U10") (pin "65") (pinfunction "PE5_65") (pintype "bidirectional"))
      (node (ref "U9") (pin "2") (pinfunction "A_2") (pintype "input"))
    )
    (net (code "100") (name "US2-CLK-TFT") (class "Default")
      (node (ref "U10") (pin "22") (pinfunction "PC4_22") (pintype "bidirectional"))
      (node (ref "U7") (pin "36") (pinfunction "~{WR}/SCL_36") (pintype "bidirectional"))
    )
    (net (code "101") (name "US2-CS-TFT") (class "Default")
      (node (ref "R35") (pin "P$1") (pinfunction "P$1_P$1") (pintype "bidirectional"))
      (node (ref "U10") (pin "23") (pinfunction "PC5_23") (pintype "bidirectional"))
      (node (ref "U7") (pin "38") (pinfunction "~{CS}_38") (pintype "bidirectional"))
    )
    (net (code "102") (name "US2-MISO-TFT") (class "Default")
      (node (ref "U10") (pin "21") (pinfunction "PC3_21") (pintype "bidirectional"))
      (node (ref "U7") (pin "33") (pinfunction "SDO_33") (pintype "bidirectional"))
    )
    (net (code "103") (name "US2-MOSI-TFT") (class "Default")
      (node (ref "U10") (pin "20") (pinfunction "PC2_20") (pintype "bidirectional"))
      (node (ref "U7") (pin "34") (pinfunction "SDA_34") (pintype "bidirectional"))
    )
    (net (code "104") (name "USB-RST") (class "Default")
      (node (ref "U10") (pin "3") (pinfunction "PA2_3") (pintype "bidirectional"))
      (node (ref "U6") (pin "9") (pinfunction "RSTB_9") (pintype "bidirectional"))
    )
    (net (code "105") (name "USB-SUS") (class "Default")
      (node (ref "U10") (pin "2") (pinfunction "PA1_2") (pintype "bidirectional"))
      (node (ref "U6") (pin "17") (pinfunction "SUSPEND_17") (pintype "bidirectional"))
    )
    (net (code "106") (name "USB-UART-D+") (class "Default")
      (node (ref "D4") (pin "3") (pinfunction "3_3") (pintype "bidirectional"))
      (node (ref "J10") (pin "A6") (pinfunction "DP_A6") (pintype "bidirectional"))
      (node (ref "J10") (pin "B6") (pinfunction "DP_B6") (pintype "bidirectional"))
      (node (ref "U6") (pin "3") (pinfunction "D+_3") (pintype "bidirectional"))
    )
    (net (code "107") (name "USB-UART-D-") (class "Default")
      (node (ref "D4") (pin "2") (pinfunction "2_2") (pintype "bidirectional"))
      (node (ref "J10") (pin "A7") (pinfunction "DN_A7") (pintype "bidirectional"))
      (node (ref "J10") (pin "B7") (pinfunction "DN_B7") (pintype "bidirectional"))
      (node (ref "U6") (pin "4") (pinfunction "D-_4") (pintype "bidirectional"))
    )
    (net (code "108") (name "V-USB") (class "Default")
      (node (ref "D4") (pin "4") (pinfunction "4_4") (pintype "bidirectional"))
      (node (ref "J10") (pin "A4_B9") (pinfunction "VBUS_A4_B9") (pintype "bidirectional"))
      (node (ref "J10") (pin "B4_A9") (pinfunction "VBUS_B4_A9") (pintype "bidirectional"))
      (node (ref "R30") (pin "P$2") (pinfunction "P$2_P$2") (pintype "bidirectional"))
    )
    (net (code "109") (name "VIN-SENSE") (class "Default")
      (node (ref "C7") (pin "P$1") (pinfunction "P$1_P$1") (pintype "bidirectional"))
      (node (ref "R8") (pin "P$1") (pinfunction "P$1_P$1") (pintype "bidirectional"))
      (node (ref "R9") (pin "P$2") (pinfunction "P$2_P$2") (pintype "bidirectional"))
      (node (ref "U10") (pin "46") (pinfunction "PD0_46") (pintype "bidirectional"))
    )
    (net (code "110") (name "WTIM1-CC1-ZERO-CROSS") (class "Default")
      (node (ref "J8") (pin "P$2") (pinfunction "S_P$2") (pintype "passive"))
      (node (ref "R28") (pin "P$1") (pinfunction "P$1_P$1") (pintype "bidirectional"))
      (node (ref "U10") (pin "64") (pinfunction "PE4_64") (pintype "bidirectional"))
    )
    (net (code "111") (name "WTIM2-CC0-SERVO0-SIG") (class "Default")
      (node (ref "U10") (pin "49") (pinfunction "PD3_49") (pintype "bidirectional"))
      (node (ref "U5") (pin "2") (pinfunction "A_2") (pintype "input"))
    )
    (net (code "112") (name "unconnected-(D14-CLKO-Pad6)") (class "Default")
      (node (ref "D14") (pin "6") (pinfunction "CLKO_6") (pintype "bidirectional"))
    )
    (net (code "113") (name "unconnected-(D14-SDO-Pad1)") (class "Default")
      (node (ref "D14") (pin "1") (pinfunction "SDO_1") (pintype "bidirectional"))
    )
    (net (code "114") (name "unconnected-(J10-SBU1-PadA8)") (class "Default")
      (node (ref "J10") (pin "A8") (pinfunction "SBU1_A8") (pintype "bidirectional"))
    )
    (net (code "115") (name "unconnected-(J10-SBU2-PadB8)") (class "Default")
      (node (ref "J10") (pin "B8") (pinfunction "SBU2_B8") (pintype "bidirectional"))
    )
    (net (code "116") (name "unconnected-(M1-CTS-Pad3)") (class "Default")
      (node (ref "M1") (pin "3") (pinfunction "CTS_3") (pintype "bidirectional"))
    )
    (net (code "117") (name "unconnected-(M1-PIO2-Pad14)") (class "Default")
      (node (ref "M1") (pin "14") (pinfunction "PIO2_14") (pintype "bidirectional"))
    )
    (net (code "118") (name "unconnected-(M1-PIO3-Pad13)") (class "Default")
      (node (ref "M1") (pin "13") (pinfunction "PIO3_13") (pintype "bidirectional"))
    )
    (net (code "119") (name "unconnected-(M1-RTS-Pad1)") (class "Default")
      (node (ref "M1") (pin "1") (pinfunction "RTS_1") (pintype "bidirectional"))
    )
    (net (code "120") (name "unconnected-(TC1F-S-Pad5)") (class "Default")
      (node (ref "TC1") (pin "5") (pinfunction "S_5") (pintype "passive"))
    )
    (net (code "121") (name "unconnected-(TC1H-S-Pad7)") (class "Default")
      (node (ref "TC1") (pin "7") (pinfunction "S_7") (pintype "passive"))
    )
    (net (code "122") (name "unconnected-(TC1I-S-Pad8)") (class "Default")
      (node (ref "TC1") (pin "8") (pinfunction "S_8") (pintype "passive"))
    )
    (net (code "123") (name "unconnected-(U2-ALERT4-Pad15)") (class "Default")
      (node (ref "U2") (pin "15") (pinfunction "ALERT4_15") (pintype "bidirectional"))
    )
    (net (code "124") (name "unconnected-(U2-ALRT1-Pad11)") (class "Default")
      (node (ref "U2") (pin "11") (pinfunction "ALRT1_11") (pintype "bidirectional"))
    )
    (net (code "125") (name "unconnected-(U2-ALRT2-Pad12)") (class "Default")
      (node (ref "U2") (pin "12") (pinfunction "ALRT2_12") (pintype "bidirectional"))
    )
    (net (code "126") (name "unconnected-(U2-ALRT3-Pad14)") (class "Default")
      (node (ref "U2") (pin "14") (pinfunction "ALRT3_14") (pintype "bidirectional"))
    )
    (net (code "127") (name "unconnected-(U4-ALERT4-Pad15)") (class "Default")
      (node (ref "U4") (pin "15") (pinfunction "ALERT4_15") (pintype "bidirectional"))
    )
    (net (code "128") (name "unconnected-(U4-ALRT1-Pad11)") (class "Default")
      (node (ref "U4") (pin "11") (pinfunction "ALRT1_11") (pintype "bidirectional"))
    )
    (net (code "129") (name "unconnected-(U4-ALRT2-Pad12)") (class "Default")
      (node (ref "U4") (pin "12") (pinfunction "ALRT2_12") (pintype "bidirectional"))
    )
    (net (code "130") (name "unconnected-(U4-ALRT3-Pad14)") (class "Default")
      (node (ref "U4") (pin "14") (pinfunction "ALRT3_14") (pintype "bidirectional"))
    )
    (net (code "131") (name "unconnected-(U6-CTS-Pad18)") (class "Default")
      (node (ref "U6") (pin "18") (pinfunction "CTS_18") (pintype "bidirectional"))
    )
    (net (code "132") (name "unconnected-(U6-DCD-Pad24)") (class "Default")
      (node (ref "U6") (pin "24") (pinfunction "DCD_24") (pintype "bidirectional"))
    )
    (net (code "133") (name "unconnected-(U6-DSR-Pad22)") (class "Default")
      (node (ref "U6") (pin "22") (pinfunction "DSR_22") (pintype "bidirectional"))
    )
    (net (code "134") (name "unconnected-(U6-DTR-Pad23)") (class "Default")
      (node (ref "U6") (pin "23") (pinfunction "DTR_23") (pintype "bidirectional"))
    )
    (net (code "135") (name "unconnected-(U6-GPIO2-RS485-Pad12)") (class "Default")
      (node (ref "U6") (pin "12") (pinfunction "GPIO2-RS485_12") (pintype "bidirectional"))
    )
    (net (code "136") (name "unconnected-(U6-GPIO3-WKUP-Pad11)") (class "Default")
      (node (ref "U6") (pin "11") (pinfunction "GPIO3-WKUP_11") (pintype "bidirectional"))
    )
    (net (code "137") (name "unconnected-(U6-RI{slash}CLK-Pad1)") (class "Default")
      (node (ref "U6") (pin "1") (pinfunction "RI/CLK_1") (pintype "bidirectional"))
    )
    (net (code "138") (name "unconnected-(U6-RTS-Pad19)") (class "Default")
      (node (ref "U6") (pin "19") (pinfunction "RTS_19") (pintype "bidirectional"))
    )
    (net (code "139") (name "unconnected-(U6-SUSPENDB-Pad15)") (class "Default")
      (node (ref "U6") (pin "15") (pinfunction "SUSPENDB_15") (pintype "bidirectional"))
    )
    (net (code "140") (name "unconnected-(U10-PA0-Pad1)") (class "Default")
      (node (ref "U10") (pin "1") (pinfunction "PA0_1") (pintype "bidirectional"))
    )
    (net (code "141") (name "unconnected-(U10-PA5-Pad6)") (class "Default")
      (node (ref "U10") (pin "6") (pinfunction "PA5_6") (pintype "bidirectional"))
    )
    (net (code "142") (name "unconnected-(U10-PA6-Pad7)") (class "Default")
      (node (ref "U10") (pin "7") (pinfunction "PA6_7") (pintype "bidirectional"))
    )
    (net (code "143") (name "unconnected-(U10-PA7-Pad26)") (class "Default")
      (node (ref "U10") (pin "26") (pinfunction "PA7_26") (pintype "bidirectional"))
    )
    (net (code "144") (name "unconnected-(U10-PA9-Pad28)") (class "Default")
      (node (ref "U10") (pin "28") (pinfunction "PA9_28") (pintype "bidirectional"))
    )
    (net (code "145") (name "unconnected-(U10-PA10-Pad29)") (class "Default")
      (node (ref "U10") (pin "29") (pinfunction "PA10_29") (pintype "bidirectional"))
    )
    (net (code "146") (name "unconnected-(U10-PA11-Pad30)") (class "Default")
      (node (ref "U10") (pin "30") (pinfunction "PA11_30") (pintype "bidirectional"))
    )
    (net (code "147") (name "unconnected-(U10-PA12-Pad33)") (class "Default")
      (node (ref "U10") (pin "33") (pinfunction "PA12_33") (pintype "bidirectional"))
    )
    (net (code "148") (name "unconnected-(U10-PA13-Pad34)") (class "Default")
      (node (ref "U10") (pin "34") (pinfunction "PA13_34") (pintype "bidirectional"))
    )
    (net (code "149") (name "unconnected-(U10-PA14-Pad35)") (class "Default")
      (node (ref "U10") (pin "35") (pinfunction "PA14_35") (pintype "bidirectional"))
    )
    (net (code "150") (name "unconnected-(U10-PA15-Pad100)") (class "Default")
      (node (ref "U10") (pin "100") (pinfunction "PA15_100") (pintype "bidirectional"))
    )
    (net (code "151") (name "unconnected-(U10-PB1-Pad10)") (class "Default")
      (node (ref "U10") (pin "10") (pinfunction "PB1_10") (pintype "bidirectional"))
    )
    (net (code "152") (name "unconnected-(U10-PB2-Pad11)") (class "Default")
      (node (ref "U10") (pin "11") (pinfunction "PB2_11") (pintype "bidirectional"))
    )
    (net (code "153") (name "unconnected-(U10-PB4-Pad13)") (class "Default")
      (node (ref "U10") (pin "13") (pinfunction "PB4_13") (pintype "bidirectional"))
    )
    (net (code "154") (name "unconnected-(U10-PB9-Pad37)") (class "Default")
      (node (ref "U10") (pin "37") (pinfunction "PB9_37") (pintype "bidirectional"))
    )
    (net (code "155") (name "unconnected-(U10-PB10-Pad38)") (class "Default")
      (node (ref "U10") (pin "38") (pinfunction "PB10_38") (pintype "bidirectional"))
    )
    (net (code "156") (name "unconnected-(U10-PC0-Pad18)") (class "Default")
      (node (ref "U10") (pin "18") (pinfunction "PC0_18") (pintype "bidirectional"))
    )
    (net (code "157") (name "unconnected-(U10-PC6-Pad55)") (class "Default")
      (node (ref "U10") (pin "55") (pinfunction "PC6_55") (pintype "bidirectional"))
    )
    (net (code "158") (name "unconnected-(U10-PC11-Pad71)") (class "Default")
      (node (ref "U10") (pin "71") (pinfunction "PC11_71") (pintype "bidirectional"))
    )
    (net (code "159") (name "unconnected-(U10-PD1-Pad47)") (class "Default")
      (node (ref "U10") (pin "47") (pinfunction "PD1_47") (pintype "bidirectional"))
    )
    (net (code "160") (name "unconnected-(U10-PD8-Pad54)") (class "Default")
      (node (ref "U10") (pin "54") (pinfunction "PD8_54") (pintype "bidirectional"))
    )
    (net (code "161") (name "unconnected-(U10-PE6-Pad66)") (class "Default")
      (node (ref "U10") (pin "66") (pinfunction "PE6_66") (pintype "bidirectional"))
    )
    (net (code "162") (name "unconnected-(U10-PE14-Pad98)") (class "Default")
      (node (ref "U10") (pin "98") (pinfunction "PE14_98") (pintype "bidirectional"))
    )
    (net (code "163") (name "unconnected-(U10-PE15-Pad99)") (class "Default")
      (node (ref "U10") (pin "99") (pinfunction "PE15_99") (pintype "bidirectional"))
    )
    (net (code "164") (name "unconnected-(U10-PF5-Pad81)") (class "Default")
      (node (ref "U10") (pin "81") (pinfunction "PF5_81") (pintype "bidirectional"))
    )
    (net (code "165") (name "unconnected-(U10-PF9-Pad87)") (class "Default")
      (node (ref "U10") (pin "87") (pinfunction "PF9_87") (pintype "bidirectional"))
    )
    (net (code "166") (name "unconnected-(U10-PF10-Pad74)") (class "Default")
      (node (ref "U10") (pin "74") (pinfunction "PF10_74") (pintype "bidirectional"))
    )
    (net (code "167") (name "unconnected-(U10-PF11-Pad75)") (class "Default")
      (node (ref "U10") (pin "75") (pinfunction "PF11_75") (pintype "bidirectional"))
    )
    (net (code "168") (name "unconnected-(U10-PF12-Pad80)") (class "Default")
      (node (ref "U10") (pin "80") (pinfunction "PF12_80") (pintype "bidirectional"))
    )
  )
)
